# dw08a.net
KiCad netlist of a schematic drawn in EAGLE
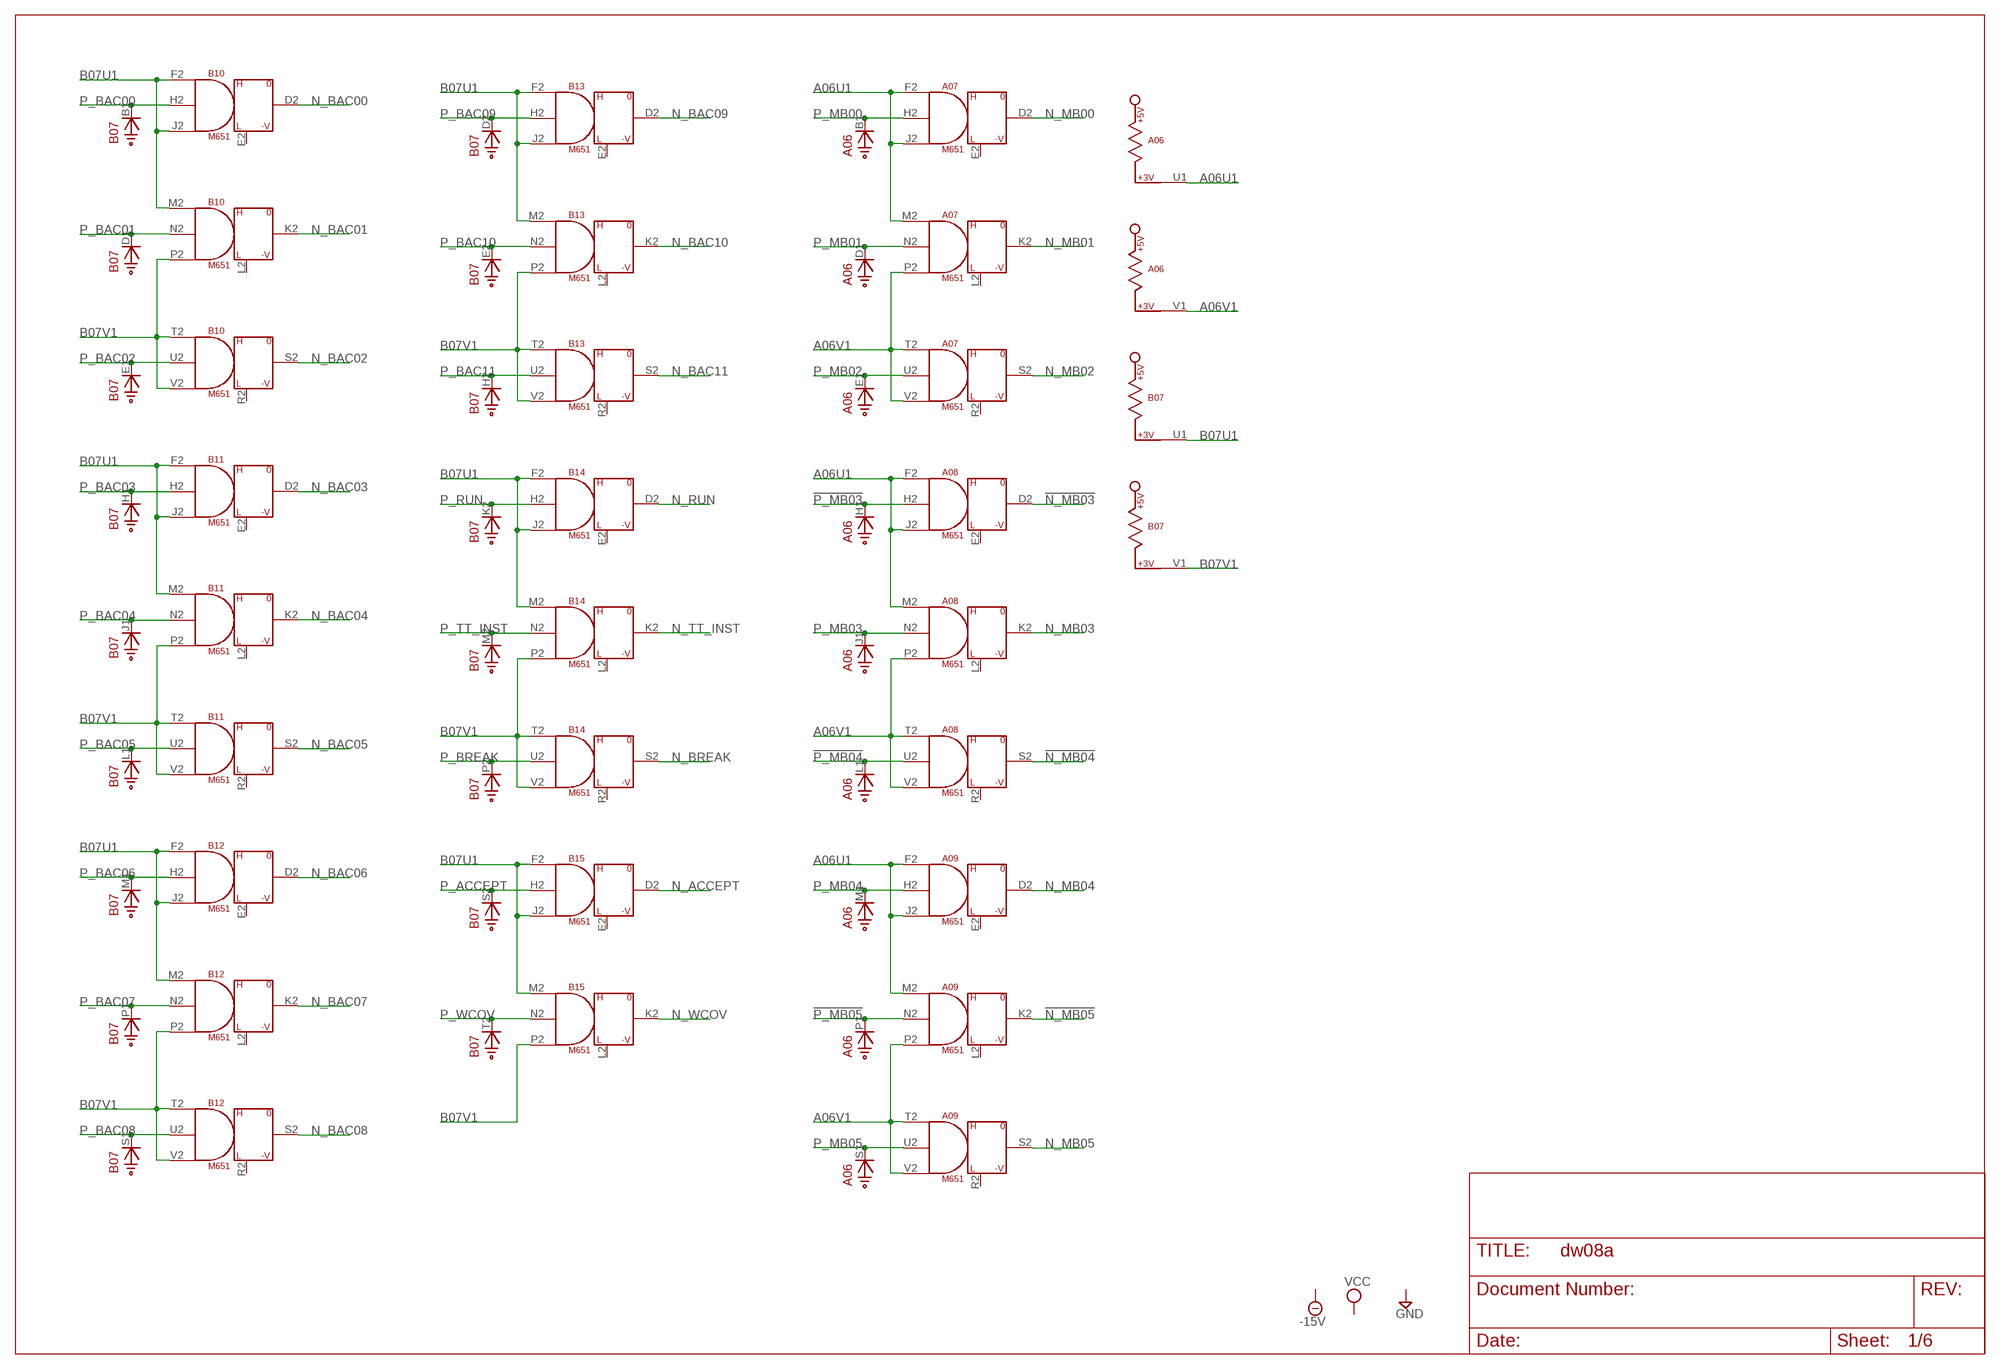
[diagram p0: schematic, sheet 1]
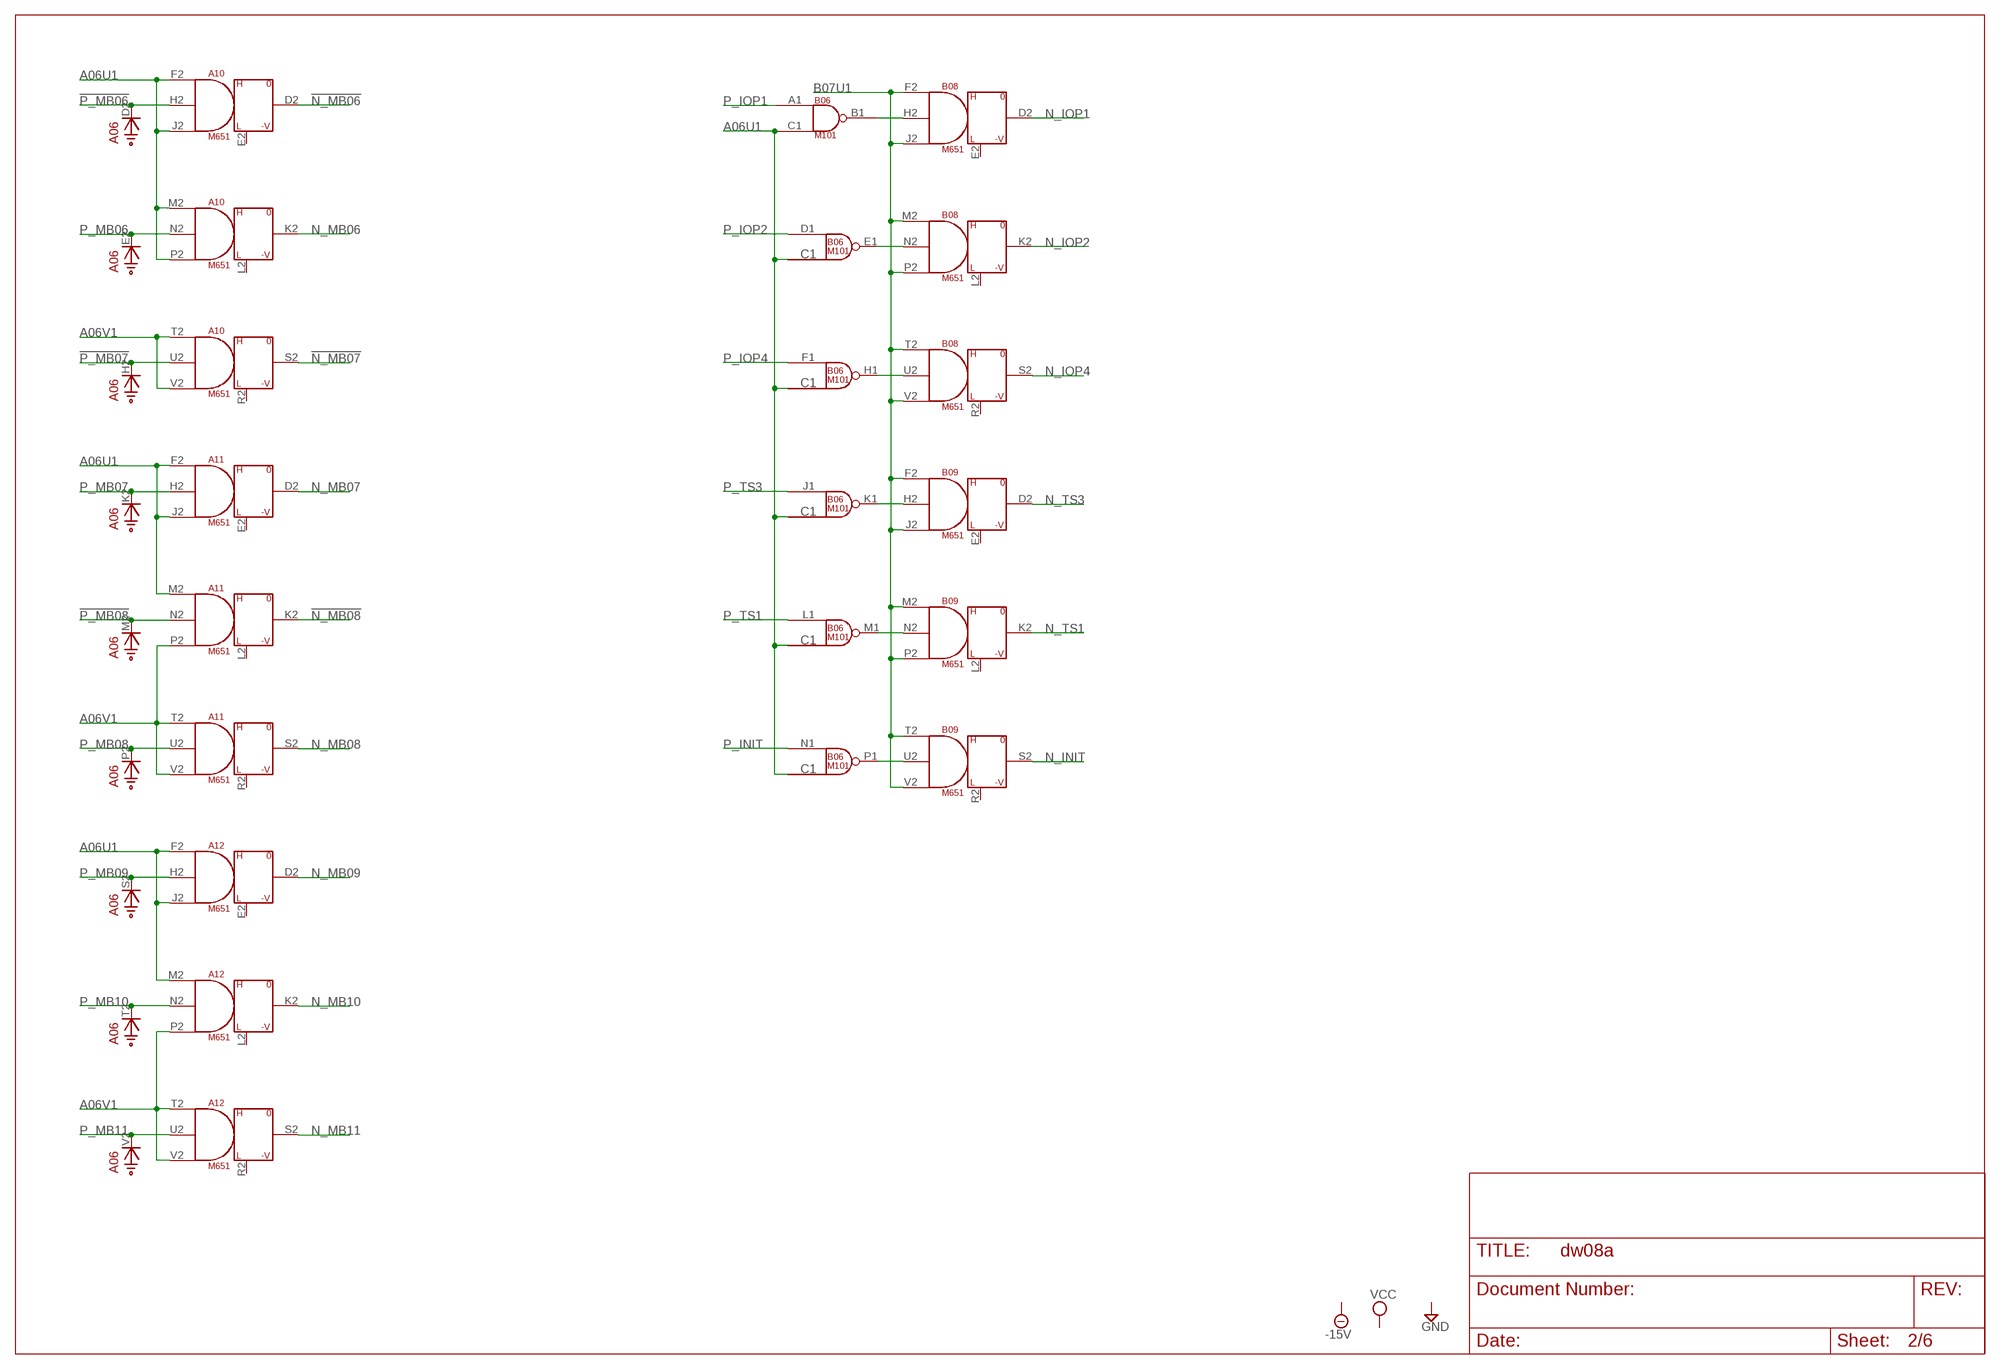
[diagram p1: schematic, sheet 2]
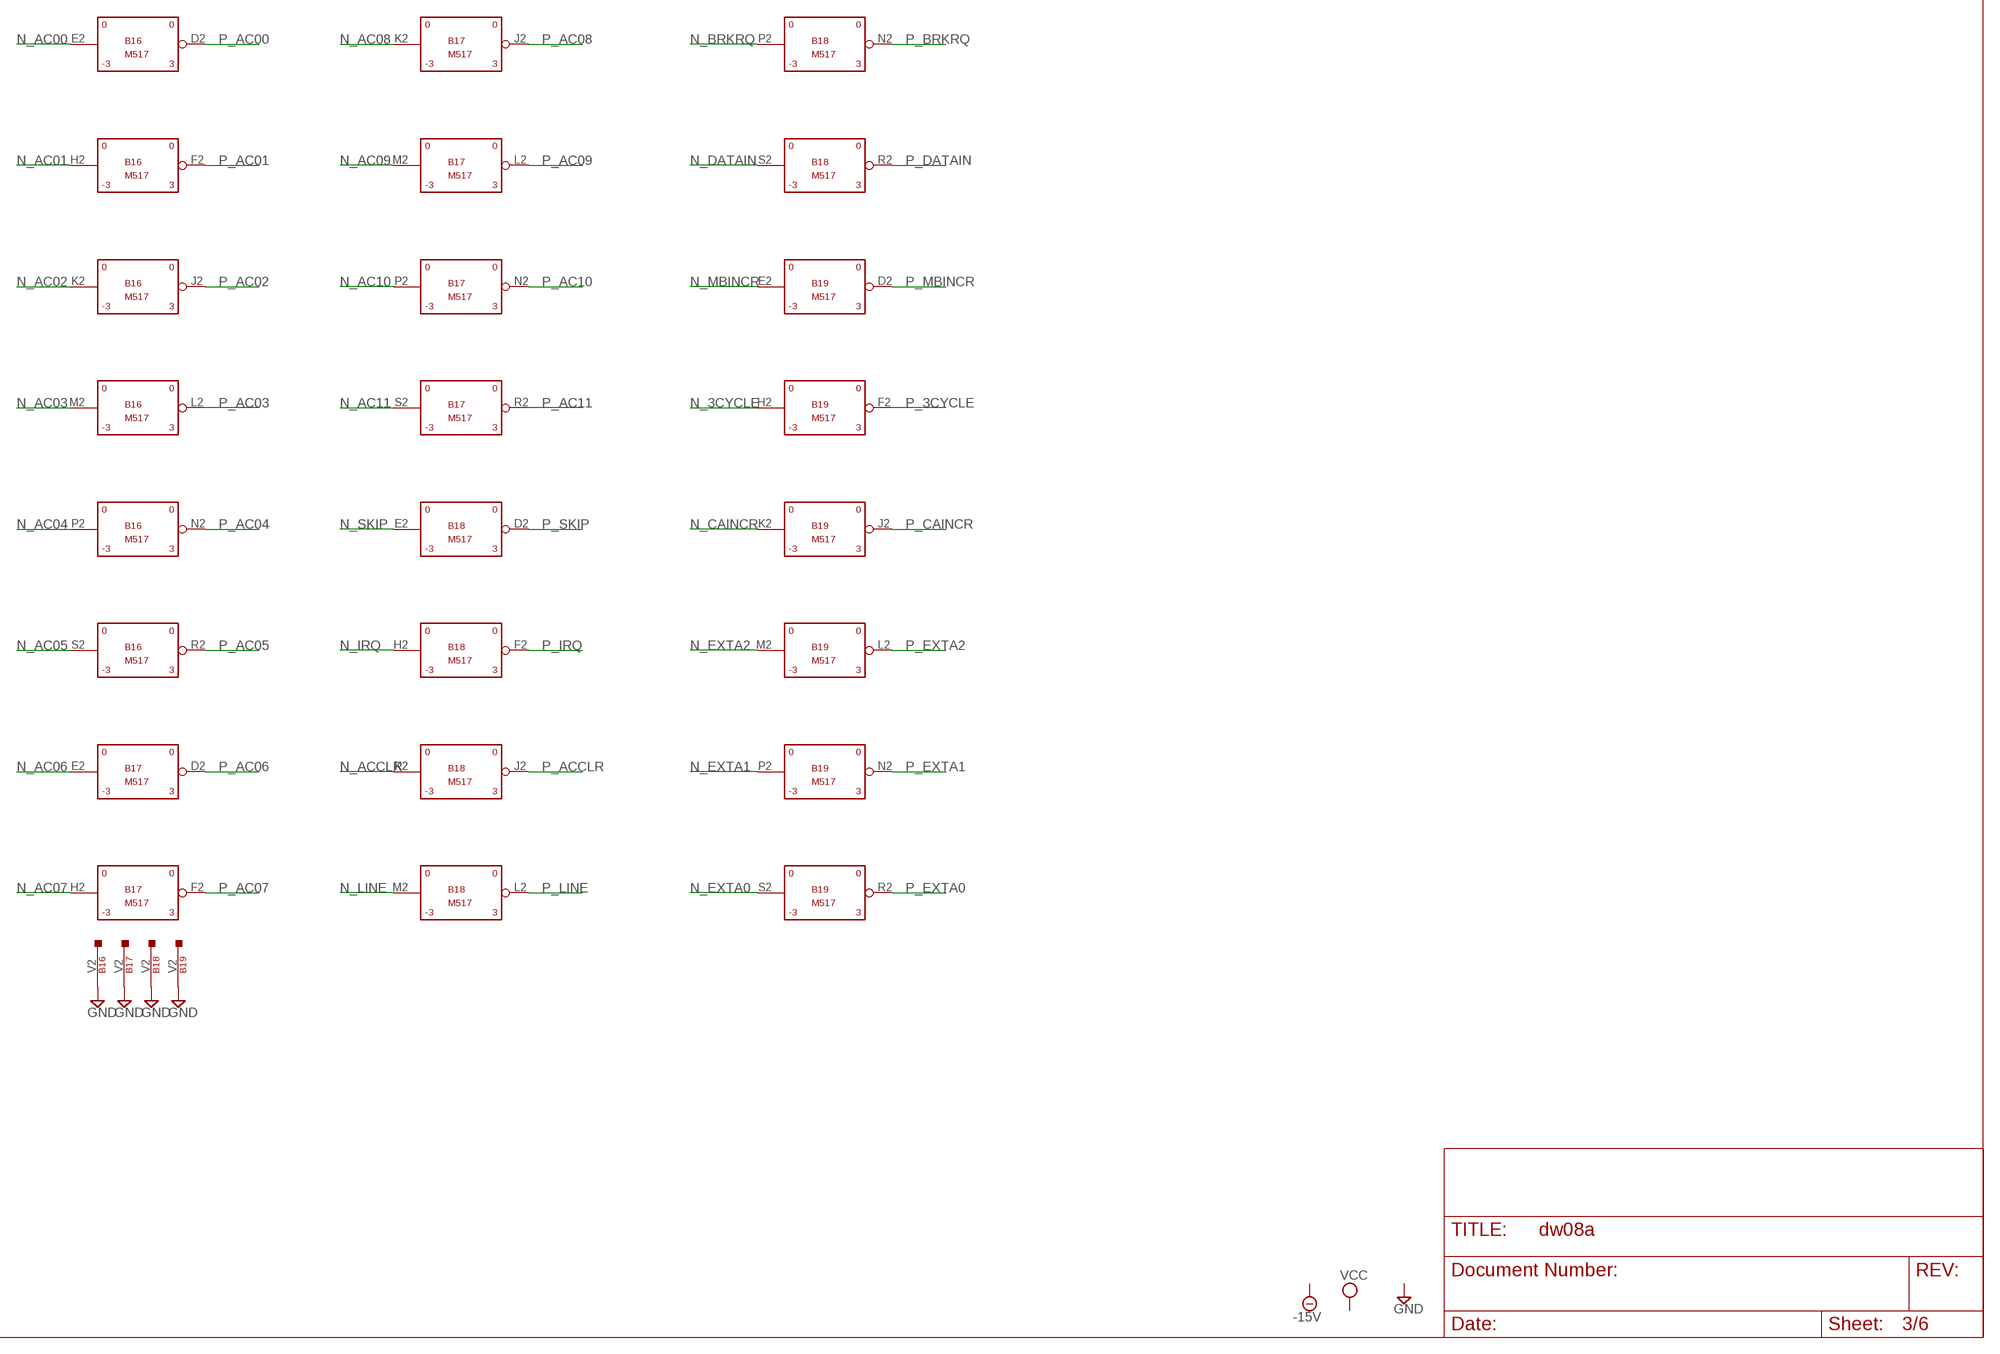
[diagram p2: schematic, sheet 3]
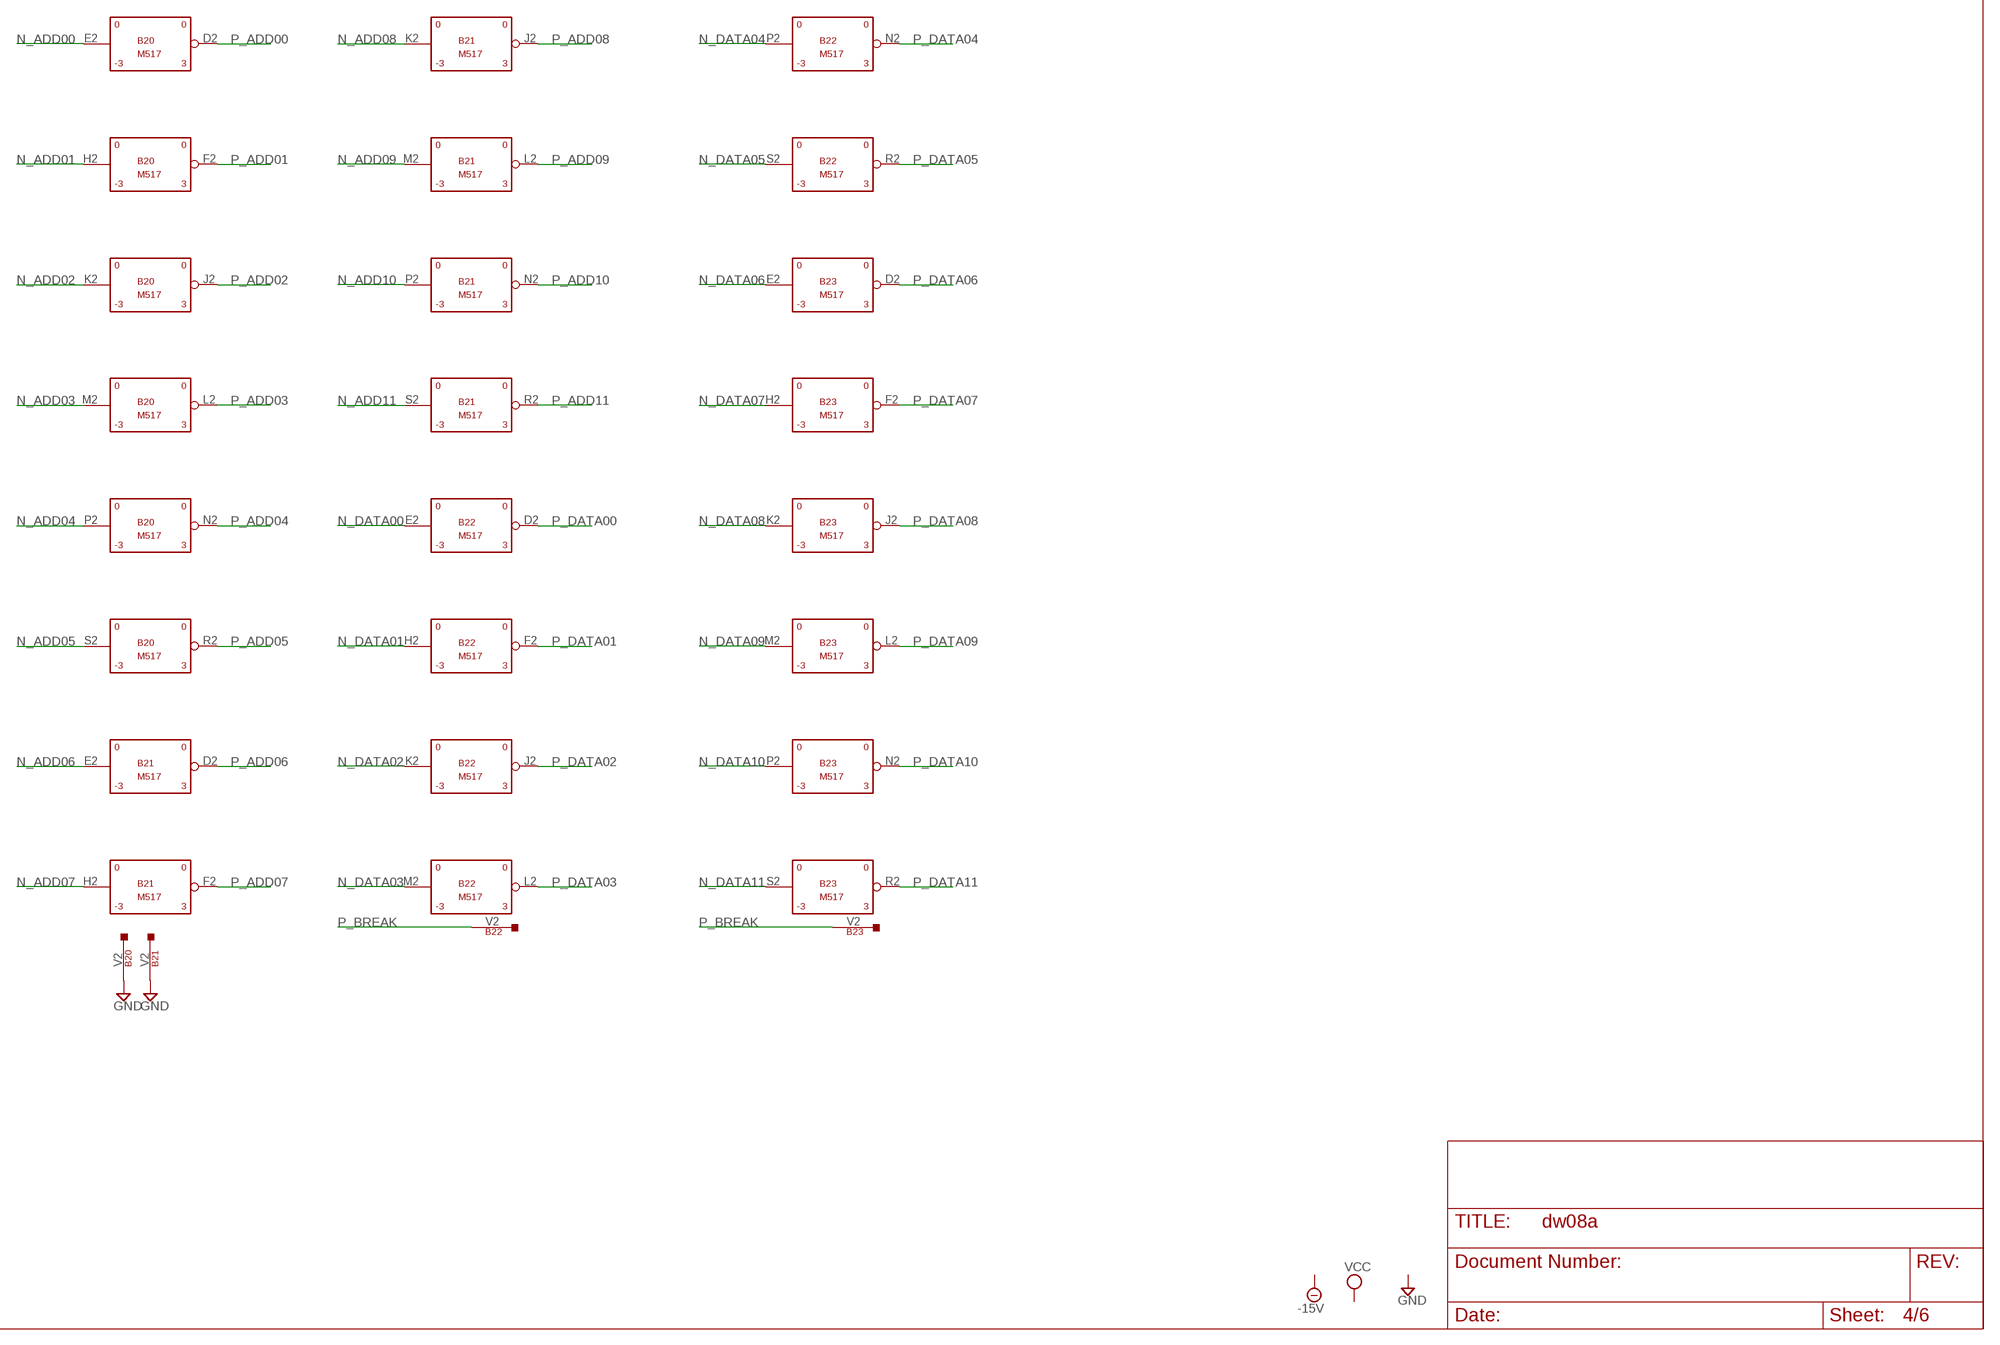
[diagram p3: schematic, sheet 4]
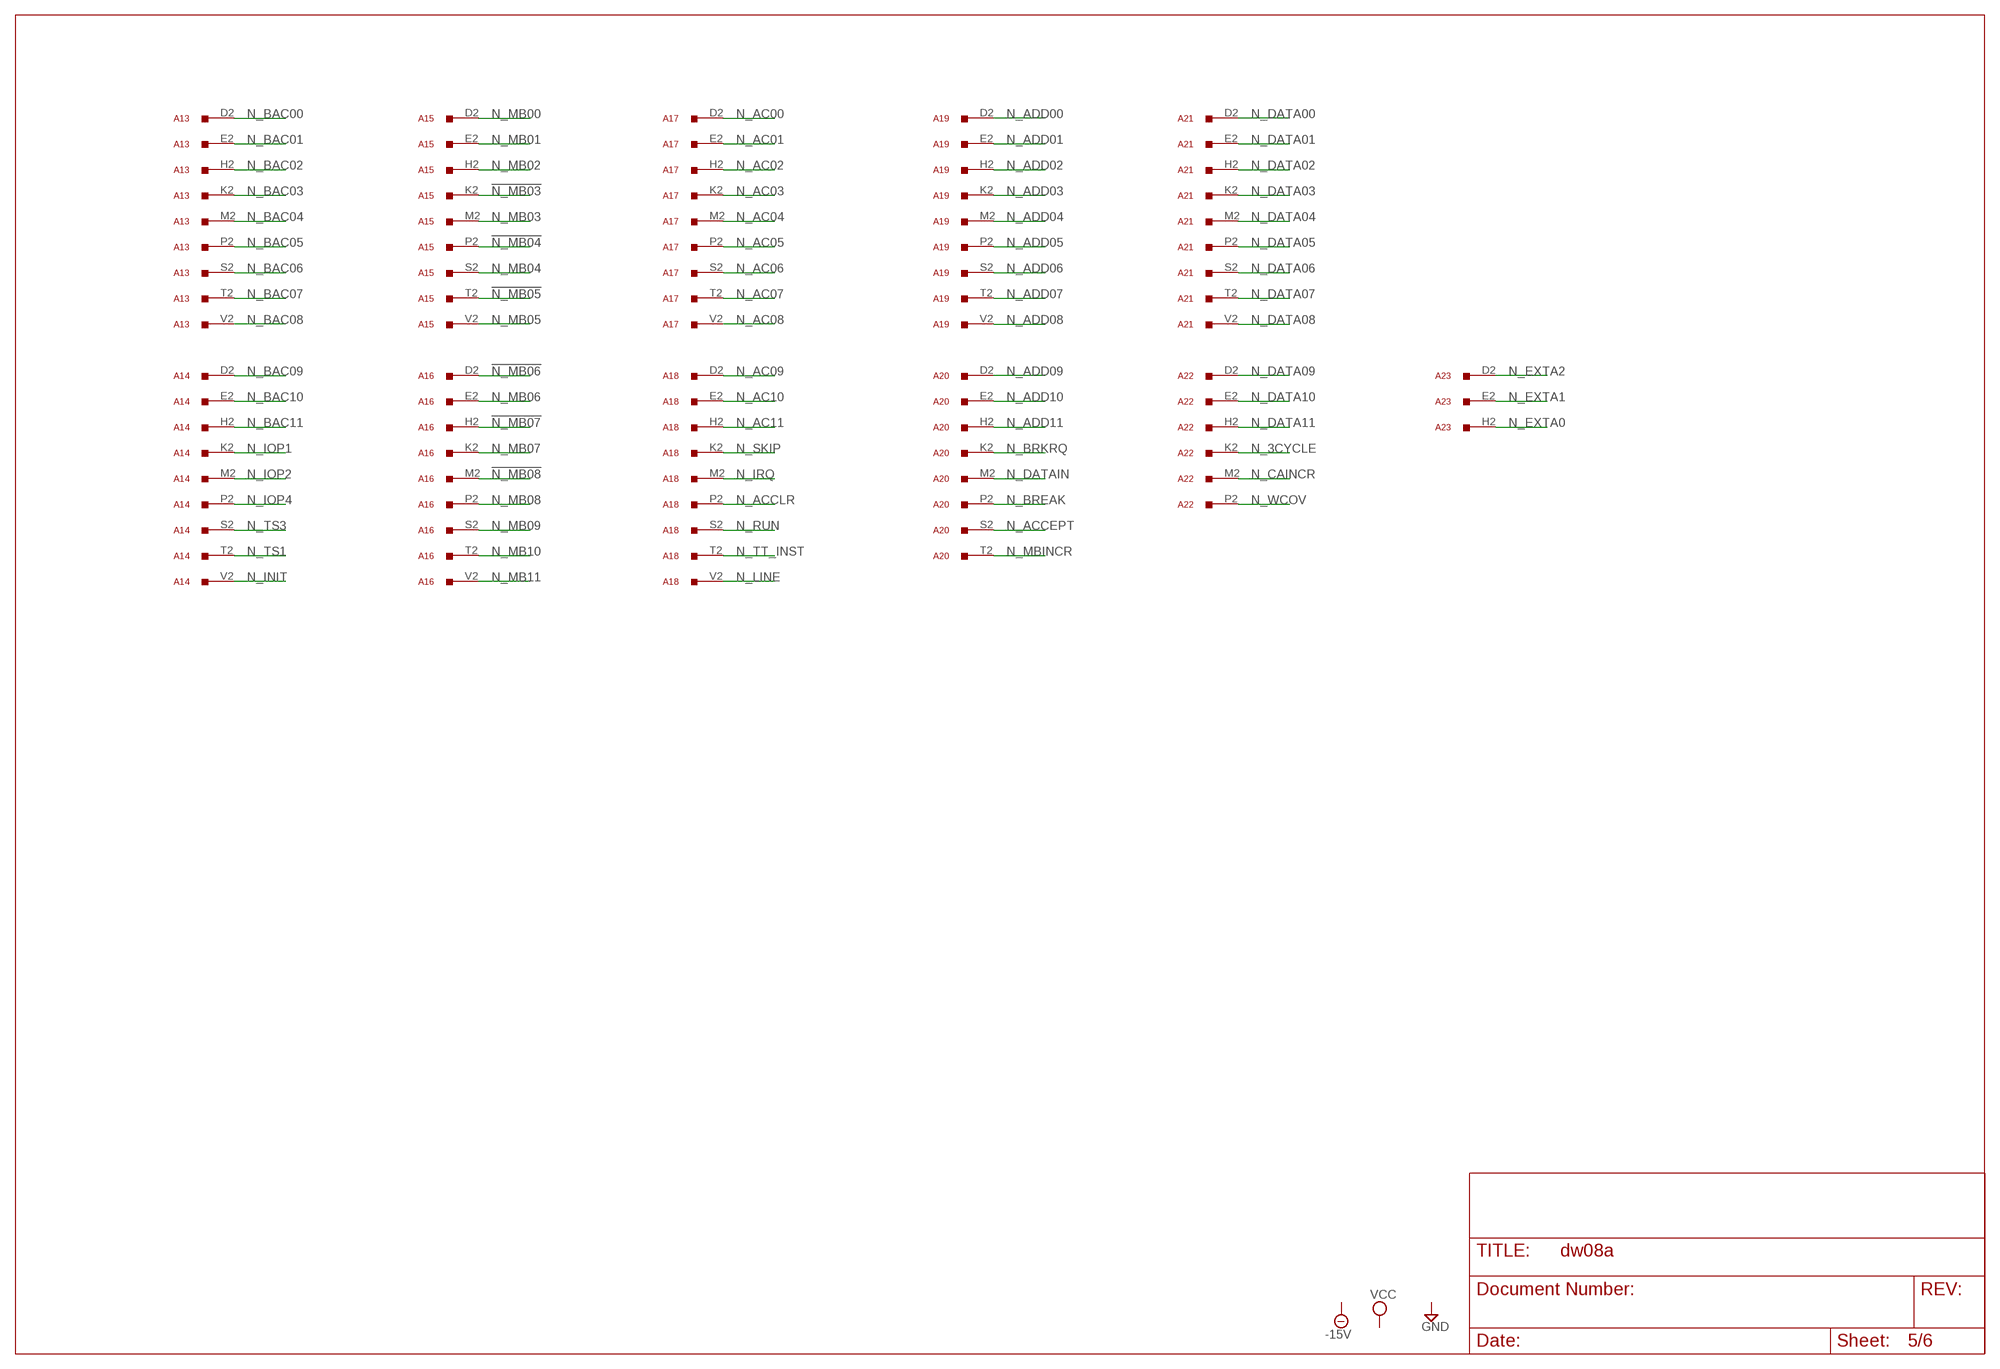
[diagram p4: schematic, sheet 5]
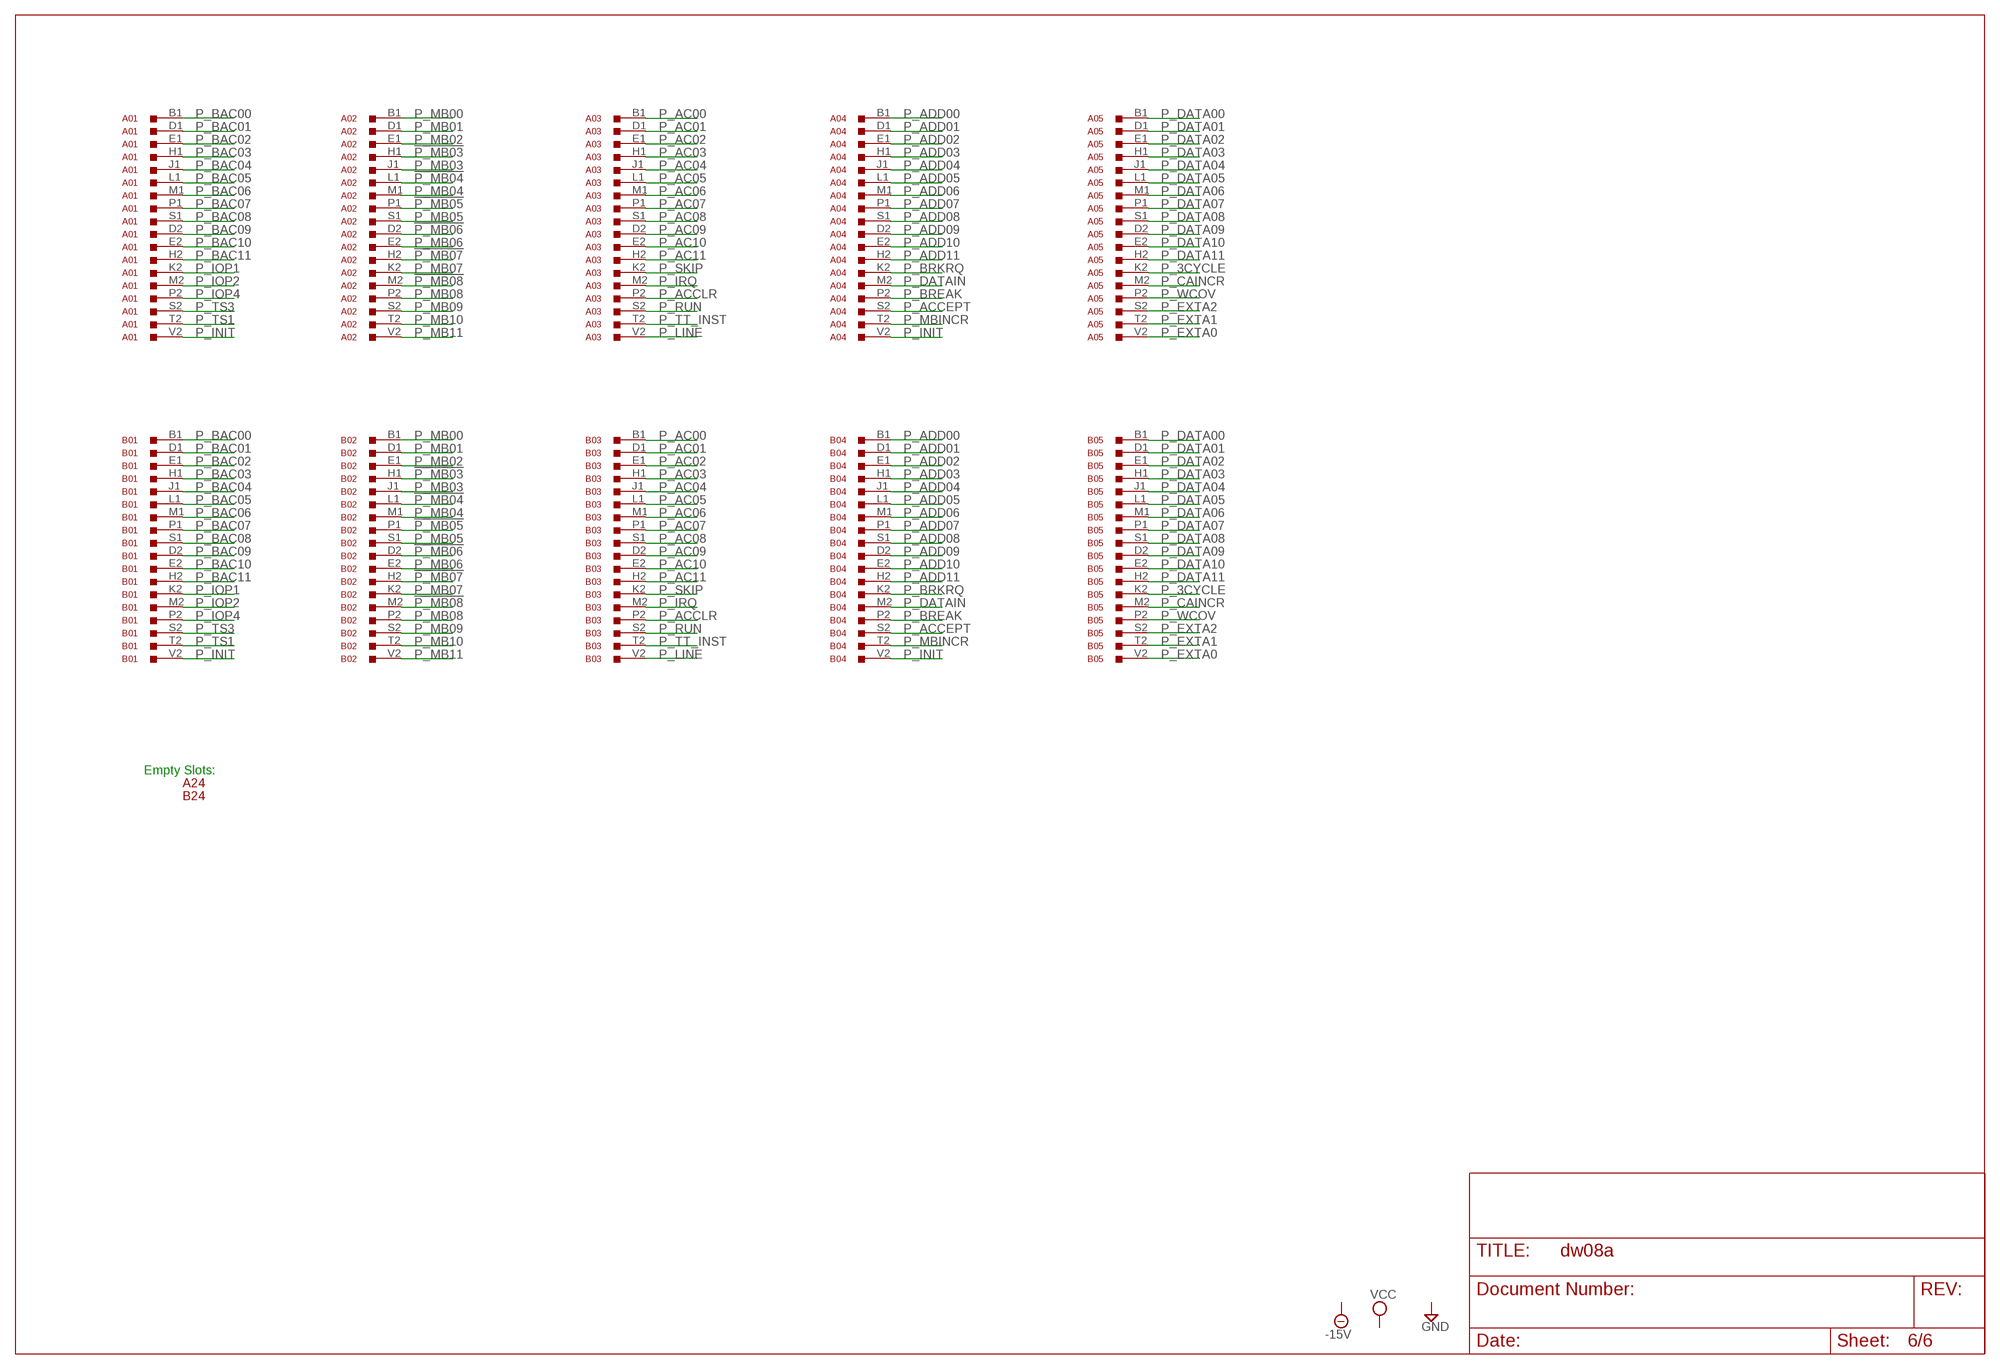
[diagram p5: schematic, sheet 6]

(export (version "E")
  (design (tool "Eeschema 10.0.6"))
  (components
    (comp (ref "A01")
      (value "M903")
      (footprint "eagle-import:H807")
      (libsource (lib "eagle-import") (part "M903"))
    )
    (comp (ref "A02")
      (value "M903")
      (footprint "eagle-import:H807")
      (libsource (lib "eagle-import") (part "M903"))
    )
    (comp (ref "A03")
      (value "M903")
      (footprint "eagle-import:H807")
      (libsource (lib "eagle-import") (part "M903"))
    )
    (comp (ref "A04")
      (value "M903")
      (footprint "eagle-import:H807")
      (libsource (lib "eagle-import") (part "M903"))
    )
    (comp (ref "A05")
      (value "M903")
      (footprint "eagle-import:H807")
      (libsource (lib "eagle-import") (part "M903"))
    )
    (comp (ref "A24")
      (value "H807")
      (footprint "eagle-import:H807")
      (libsource (lib "eagle-import") (part "H807"))
    )
    (comp (ref "B01")
      (value "M903")
      (footprint "eagle-import:H807")
      (libsource (lib "eagle-import") (part "M903"))
    )
    (comp (ref "B02")
      (value "M903")
      (footprint "eagle-import:H807")
      (libsource (lib "eagle-import") (part "M903"))
    )
    (comp (ref "B03")
      (value "M903")
      (footprint "eagle-import:H807")
      (libsource (lib "eagle-import") (part "M903"))
    )
    (comp (ref "B04")
      (value "M903")
      (footprint "eagle-import:H807")
      (libsource (lib "eagle-import") (part "M903"))
    )
    (comp (ref "B05")
      (value "M903")
      (footprint "eagle-import:H807")
      (libsource (lib "eagle-import") (part "M903"))
    )
    (comp (ref "B24")
      (value "H807")
      (footprint "eagle-import:H807")
      (libsource (lib "eagle-import") (part "H807"))
    )
    (comp (ref "A13")
      (value "W011")
      (footprint "eagle-import:H807")
      (libsource (lib "eagle-import") (part "W011"))
    )
    (comp (ref "A14")
      (value "W011")
      (footprint "eagle-import:H807")
      (libsource (lib "eagle-import") (part "W011"))
    )
    (comp (ref "A15")
      (value "W011")
      (footprint "eagle-import:H807")
      (libsource (lib "eagle-import") (part "W011"))
    )
    (comp (ref "A16")
      (value "W011")
      (footprint "eagle-import:H807")
      (libsource (lib "eagle-import") (part "W011"))
    )
    (comp (ref "A17")
      (value "W011")
      (footprint "eagle-import:H807")
      (libsource (lib "eagle-import") (part "W011"))
    )
    (comp (ref "A18")
      (value "W011")
      (footprint "eagle-import:H807")
      (libsource (lib "eagle-import") (part "W011"))
    )
    (comp (ref "A19")
      (value "W011")
      (footprint "eagle-import:H807")
      (libsource (lib "eagle-import") (part "W011"))
    )
    (comp (ref "A20")
      (value "W011")
      (footprint "eagle-import:H807")
      (libsource (lib "eagle-import") (part "W011"))
    )
    (comp (ref "A21")
      (value "W011")
      (footprint "eagle-import:H807")
      (libsource (lib "eagle-import") (part "W011"))
    )
    (comp (ref "A22")
      (value "W011")
      (footprint "eagle-import:H807")
      (libsource (lib "eagle-import") (part "W011"))
    )
    (comp (ref "A23")
      (value "W011")
      (footprint "eagle-import:H807")
      (libsource (lib "eagle-import") (part "W011"))
    )
    (comp (ref "A06")
      (value "M907")
      (footprint "eagle-import:H807")
      (libsource (lib "eagle-import") (part "M907"))
    )
    (comp (ref "A10")
      (value "M651")
      (footprint "eagle-import:H807")
      (libsource (lib "eagle-import") (part "M651"))
    )
    (comp (ref "A11")
      (value "M651")
      (footprint "eagle-import:H807")
      (libsource (lib "eagle-import") (part "M651"))
    )
    (comp (ref "A12")
      (value "M651")
      (footprint "eagle-import:H807")
      (libsource (lib "eagle-import") (part "M651"))
    )
    (comp (ref "B06")
      (value "M101")
      (footprint "eagle-import:H807")
      (libsource (lib "eagle-import") (part "M101"))
    )
    (comp (ref "B08")
      (value "M651")
      (footprint "eagle-import:H807")
      (libsource (lib "eagle-import") (part "M651"))
    )
    (comp (ref "B09")
      (value "M651")
      (footprint "eagle-import:H807")
      (libsource (lib "eagle-import") (part "M651"))
    )
    (comp (ref "B16")
      (value "M517")
      (footprint "eagle-import:H807")
      (libsource (lib "eagle-import") (part "M517"))
    )
    (comp (ref "B17")
      (value "M517")
      (footprint "eagle-import:H807")
      (libsource (lib "eagle-import") (part "M517"))
    )
    (comp (ref "B18")
      (value "M517")
      (footprint "eagle-import:H807")
      (libsource (lib "eagle-import") (part "M517"))
    )
    (comp (ref "B19")
      (value "M517")
      (footprint "eagle-import:H807")
      (libsource (lib "eagle-import") (part "M517"))
    )
    (comp (ref "A07")
      (value "M651")
      (footprint "eagle-import:H807")
      (libsource (lib "eagle-import") (part "M651"))
    )
    (comp (ref "A08")
      (value "M651")
      (footprint "eagle-import:H807")
      (libsource (lib "eagle-import") (part "M651"))
    )
    (comp (ref "A09")
      (value "M651")
      (footprint "eagle-import:H807")
      (libsource (lib "eagle-import") (part "M651"))
    )
    (comp (ref "B07")
      (value "M907")
      (footprint "eagle-import:H807")
      (libsource (lib "eagle-import") (part "M907"))
    )
    (comp (ref "B10")
      (value "M651")
      (footprint "eagle-import:H807")
      (libsource (lib "eagle-import") (part "M651"))
    )
    (comp (ref "B11")
      (value "M651")
      (footprint "eagle-import:H807")
      (libsource (lib "eagle-import") (part "M651"))
    )
    (comp (ref "B12")
      (value "M651")
      (footprint "eagle-import:H807")
      (libsource (lib "eagle-import") (part "M651"))
    )
    (comp (ref "B13")
      (value "M651")
      (footprint "eagle-import:H807")
      (libsource (lib "eagle-import") (part "M651"))
    )
    (comp (ref "B14")
      (value "M651")
      (footprint "eagle-import:H807")
      (libsource (lib "eagle-import") (part "M651"))
    )
    (comp (ref "B15")
      (value "M651")
      (footprint "eagle-import:H807")
      (libsource (lib "eagle-import") (part "M651"))
    )
    (comp (ref "B20")
      (value "M517")
      (footprint "eagle-import:H807")
      (libsource (lib "eagle-import") (part "M517"))
    )
    (comp (ref "B21")
      (value "M517")
      (footprint "eagle-import:H807")
      (libsource (lib "eagle-import") (part "M517"))
    )
    (comp (ref "B22")
      (value "M517")
      (footprint "eagle-import:H807")
      (libsource (lib "eagle-import") (part "M517"))
    )
    (comp (ref "B23")
      (value "M517")
      (footprint "eagle-import:H807")
      (libsource (lib "eagle-import") (part "M517"))
    )
  )
  (nets
    (net (code "2") (name "A06U1") (class "Default")
      (node (ref "A06") (pin "U1") (pinfunction "P$1_U1") (pintype "passive"))
      (node (ref "A07") (pin "F2") (pinfunction "IN1_F2") (pintype "input"))
      (node (ref "A07") (pin "J2") (pinfunction "IN3_J2") (pintype "input"))
      (node (ref "A07") (pin "M2") (pinfunction "IN1_M2") (pintype "input"))
      (node (ref "A08") (pin "F2") (pinfunction "IN1_F2") (pintype "input"))
      (node (ref "A08") (pin "J2") (pinfunction "IN3_J2") (pintype "input"))
      (node (ref "A08") (pin "M2") (pinfunction "IN1_M2") (pintype "input"))
      (node (ref "A09") (pin "F2") (pinfunction "IN1_F2") (pintype "input"))
      (node (ref "A09") (pin "J2") (pinfunction "IN3_J2") (pintype "input"))
      (node (ref "A09") (pin "M2") (pinfunction "IN1_M2") (pintype "input"))
      (node (ref "A10") (pin "F2") (pinfunction "IN1_F2") (pintype "input"))
      (node (ref "A10") (pin "J2") (pinfunction "IN3_J2") (pintype "input"))
      (node (ref "A10") (pin "M2") (pinfunction "IN1_M2") (pintype "input"))
      (node (ref "A10") (pin "P2") (pinfunction "IN3_P2") (pintype "input"))
      (node (ref "A11") (pin "F2") (pinfunction "IN1_F2") (pintype "input"))
      (node (ref "A11") (pin "J2") (pinfunction "IN3_J2") (pintype "input"))
      (node (ref "A11") (pin "M2") (pinfunction "IN1_M2") (pintype "input"))
      (node (ref "A12") (pin "F2") (pinfunction "IN1_F2") (pintype "input"))
      (node (ref "A12") (pin "J2") (pinfunction "IN3_J2") (pintype "input"))
      (node (ref "A12") (pin "M2") (pinfunction "IN1_M2") (pintype "input"))
      (node (ref "B06") (pin "C1") (pinfunction "IN2_C1") (pintype "input"))
    )
    (net (code "3") (name "A06V1") (class "Default")
      (node (ref "A06") (pin "V1") (pinfunction "P$1_V1") (pintype "passive"))
      (node (ref "A07") (pin "P2") (pinfunction "IN3_P2") (pintype "input"))
      (node (ref "A07") (pin "T2") (pinfunction "IN1_T2") (pintype "input"))
      (node (ref "A07") (pin "V2") (pinfunction "IN3_V2") (pintype "input"))
      (node (ref "A08") (pin "P2") (pinfunction "IN3_P2") (pintype "input"))
      (node (ref "A08") (pin "T2") (pinfunction "IN1_T2") (pintype "input"))
      (node (ref "A08") (pin "V2") (pinfunction "IN3_V2") (pintype "input"))
      (node (ref "A09") (pin "P2") (pinfunction "IN3_P2") (pintype "input"))
      (node (ref "A09") (pin "T2") (pinfunction "IN1_T2") (pintype "input"))
      (node (ref "A09") (pin "V2") (pinfunction "IN3_V2") (pintype "input"))
      (node (ref "A10") (pin "T2") (pinfunction "IN1_T2") (pintype "input"))
      (node (ref "A10") (pin "V2") (pinfunction "IN3_V2") (pintype "input"))
      (node (ref "A11") (pin "P2") (pinfunction "IN3_P2") (pintype "input"))
      (node (ref "A11") (pin "T2") (pinfunction "IN1_T2") (pintype "input"))
      (node (ref "A11") (pin "V2") (pinfunction "IN3_V2") (pintype "input"))
      (node (ref "A12") (pin "P2") (pinfunction "IN3_P2") (pintype "input"))
      (node (ref "A12") (pin "T2") (pinfunction "IN1_T2") (pintype "input"))
      (node (ref "A12") (pin "V2") (pinfunction "IN3_V2") (pintype "input"))
    )
    (net (code "4") (name "B07U1") (class "Default")
      (node (ref "B07") (pin "U1") (pinfunction "P$1_U1") (pintype "passive"))
      (node (ref "B08") (pin "F2") (pinfunction "IN1_F2") (pintype "input"))
      (node (ref "B08") (pin "J2") (pinfunction "IN3_J2") (pintype "input"))
      (node (ref "B08") (pin "M2") (pinfunction "IN1_M2") (pintype "input"))
      (node (ref "B08") (pin "P2") (pinfunction "IN3_P2") (pintype "input"))
      (node (ref "B08") (pin "T2") (pinfunction "IN1_T2") (pintype "input"))
      (node (ref "B08") (pin "V2") (pinfunction "IN3_V2") (pintype "input"))
      (node (ref "B09") (pin "F2") (pinfunction "IN1_F2") (pintype "input"))
      (node (ref "B09") (pin "J2") (pinfunction "IN3_J2") (pintype "input"))
      (node (ref "B09") (pin "M2") (pinfunction "IN1_M2") (pintype "input"))
      (node (ref "B09") (pin "P2") (pinfunction "IN3_P2") (pintype "input"))
      (node (ref "B09") (pin "T2") (pinfunction "IN1_T2") (pintype "input"))
      (node (ref "B09") (pin "V2") (pinfunction "IN3_V2") (pintype "input"))
      (node (ref "B10") (pin "F2") (pinfunction "IN1_F2") (pintype "input"))
      (node (ref "B10") (pin "J2") (pinfunction "IN3_J2") (pintype "input"))
      (node (ref "B10") (pin "M2") (pinfunction "IN1_M2") (pintype "input"))
      (node (ref "B11") (pin "F2") (pinfunction "IN1_F2") (pintype "input"))
      (node (ref "B11") (pin "J2") (pinfunction "IN3_J2") (pintype "input"))
      (node (ref "B11") (pin "M2") (pinfunction "IN1_M2") (pintype "input"))
      (node (ref "B12") (pin "F2") (pinfunction "IN1_F2") (pintype "input"))
      (node (ref "B12") (pin "J2") (pinfunction "IN3_J2") (pintype "input"))
      (node (ref "B12") (pin "M2") (pinfunction "IN1_M2") (pintype "input"))
      (node (ref "B13") (pin "F2") (pinfunction "IN1_F2") (pintype "input"))
      (node (ref "B13") (pin "J2") (pinfunction "IN3_J2") (pintype "input"))
      (node (ref "B13") (pin "M2") (pinfunction "IN1_M2") (pintype "input"))
      (node (ref "B14") (pin "F2") (pinfunction "IN1_F2") (pintype "input"))
      (node (ref "B14") (pin "J2") (pinfunction "IN3_J2") (pintype "input"))
      (node (ref "B14") (pin "M2") (pinfunction "IN1_M2") (pintype "input"))
      (node (ref "B15") (pin "F2") (pinfunction "IN1_F2") (pintype "input"))
      (node (ref "B15") (pin "J2") (pinfunction "IN3_J2") (pintype "input"))
      (node (ref "B15") (pin "M2") (pinfunction "IN1_M2") (pintype "input"))
    )
    (net (code "5") (name "B07V1") (class "Default")
      (node (ref "B07") (pin "V1") (pinfunction "P$1_V1") (pintype "passive"))
      (node (ref "B10") (pin "P2") (pinfunction "IN3_P2") (pintype "input"))
      (node (ref "B10") (pin "T2") (pinfunction "IN1_T2") (pintype "input"))
      (node (ref "B10") (pin "V2") (pinfunction "IN3_V2") (pintype "input"))
      (node (ref "B11") (pin "P2") (pinfunction "IN3_P2") (pintype "input"))
      (node (ref "B11") (pin "T2") (pinfunction "IN1_T2") (pintype "input"))
      (node (ref "B11") (pin "V2") (pinfunction "IN3_V2") (pintype "input"))
      (node (ref "B12") (pin "P2") (pinfunction "IN3_P2") (pintype "input"))
      (node (ref "B12") (pin "T2") (pinfunction "IN1_T2") (pintype "input"))
      (node (ref "B12") (pin "V2") (pinfunction "IN3_V2") (pintype "input"))
      (node (ref "B13") (pin "P2") (pinfunction "IN3_P2") (pintype "input"))
      (node (ref "B13") (pin "T2") (pinfunction "IN1_T2") (pintype "input"))
      (node (ref "B13") (pin "V2") (pinfunction "IN3_V2") (pintype "input"))
      (node (ref "B14") (pin "P2") (pinfunction "IN3_P2") (pintype "input"))
      (node (ref "B14") (pin "T2") (pinfunction "IN1_T2") (pintype "input"))
      (node (ref "B14") (pin "V2") (pinfunction "IN3_V2") (pintype "input"))
      (node (ref "B15") (pin "P2") (pinfunction "IN3_P2") (pintype "input"))
    )
    (net (code "6") (name "GND") (class "Default")
      (node (ref "B16") (pin "V2") (pinfunction "P$1_V2") (pintype "input"))
      (node (ref "B17") (pin "V2") (pinfunction "P$1_V2") (pintype "input"))
      (node (ref "B18") (pin "V2") (pinfunction "P$1_V2") (pintype "input"))
      (node (ref "B19") (pin "V2") (pinfunction "P$1_V2") (pintype "input"))
      (node (ref "B20") (pin "V2") (pinfunction "P$1_V2") (pintype "input"))
      (node (ref "B21") (pin "V2") (pinfunction "P$1_V2") (pintype "input"))
    )
    (net (code "7") (name "N_3CYCLE") (class "Default")
      (node (ref "A22") (pin "K2") (pinfunction "P$2_K2") (pintype "bidirectional"))
      (node (ref "B19") (pin "H2") (pinfunction "IN_H2") (pintype "input"))
    )
    (net (code "8") (name "N_AC00") (class "Default")
      (node (ref "A17") (pin "D2") (pinfunction "P$2_D2") (pintype "bidirectional"))
      (node (ref "B16") (pin "E2") (pinfunction "IN_E2") (pintype "input"))
    )
    (net (code "9") (name "N_AC01") (class "Default")
      (node (ref "A17") (pin "E2") (pinfunction "P$2_E2") (pintype "bidirectional"))
      (node (ref "B16") (pin "H2") (pinfunction "IN_H2") (pintype "input"))
    )
    (net (code "10") (name "N_AC02") (class "Default")
      (node (ref "A17") (pin "H2") (pinfunction "P$2_H2") (pintype "bidirectional"))
      (node (ref "B16") (pin "K2") (pinfunction "IN_K2") (pintype "input"))
    )
    (net (code "11") (name "N_AC03") (class "Default")
      (node (ref "A17") (pin "K2") (pinfunction "P$2_K2") (pintype "bidirectional"))
      (node (ref "B16") (pin "M2") (pinfunction "IN_M2") (pintype "input"))
    )
    (net (code "12") (name "N_AC04") (class "Default")
      (node (ref "A17") (pin "M2") (pinfunction "P$2_M2") (pintype "bidirectional"))
      (node (ref "B16") (pin "P2") (pinfunction "IN_P2") (pintype "input"))
    )
    (net (code "13") (name "N_AC05") (class "Default")
      (node (ref "A17") (pin "P2") (pinfunction "P$2_P2") (pintype "bidirectional"))
      (node (ref "B16") (pin "S2") (pinfunction "IN_S2") (pintype "input"))
    )
    (net (code "14") (name "N_AC06") (class "Default")
      (node (ref "A17") (pin "S2") (pinfunction "P$2_S2") (pintype "bidirectional"))
      (node (ref "B17") (pin "E2") (pinfunction "IN_E2") (pintype "input"))
    )
    (net (code "15") (name "N_AC07") (class "Default")
      (node (ref "A17") (pin "T2") (pinfunction "P$2_T2") (pintype "bidirectional"))
      (node (ref "B17") (pin "H2") (pinfunction "IN_H2") (pintype "input"))
    )
    (net (code "16") (name "N_AC08") (class "Default")
      (node (ref "A17") (pin "V2") (pinfunction "P$2_V2") (pintype "bidirectional"))
      (node (ref "B17") (pin "K2") (pinfunction "IN_K2") (pintype "input"))
    )
    (net (code "17") (name "N_AC09") (class "Default")
      (node (ref "A18") (pin "D2") (pinfunction "P$2_D2") (pintype "bidirectional"))
      (node (ref "B17") (pin "M2") (pinfunction "IN_M2") (pintype "input"))
    )
    (net (code "18") (name "N_AC10") (class "Default")
      (node (ref "A18") (pin "E2") (pinfunction "P$2_E2") (pintype "bidirectional"))
      (node (ref "B17") (pin "P2") (pinfunction "IN_P2") (pintype "input"))
    )
    (net (code "19") (name "N_AC11") (class "Default")
      (node (ref "A18") (pin "H2") (pinfunction "P$2_H2") (pintype "bidirectional"))
      (node (ref "B17") (pin "S2") (pinfunction "IN_S2") (pintype "input"))
    )
    (net (code "20") (name "N_ACCEPT") (class "Default")
      (node (ref "A20") (pin "S2") (pinfunction "P$2_S2") (pintype "bidirectional"))
      (node (ref "B15") (pin "D2") (pinfunction "OUT_D2") (pintype "output"))
    )
    (net (code "21") (name "N_ACCLR") (class "Default")
      (node (ref "A18") (pin "P2") (pinfunction "P$2_P2") (pintype "bidirectional"))
      (node (ref "B18") (pin "K2") (pinfunction "IN_K2") (pintype "input"))
    )
    (net (code "22") (name "N_ADD00") (class "Default")
      (node (ref "A19") (pin "D2") (pinfunction "P$2_D2") (pintype "bidirectional"))
      (node (ref "B20") (pin "E2") (pinfunction "IN_E2") (pintype "input"))
    )
    (net (code "23") (name "N_ADD01") (class "Default")
      (node (ref "A19") (pin "E2") (pinfunction "P$2_E2") (pintype "bidirectional"))
      (node (ref "B20") (pin "H2") (pinfunction "IN_H2") (pintype "input"))
    )
    (net (code "24") (name "N_ADD02") (class "Default")
      (node (ref "A19") (pin "H2") (pinfunction "P$2_H2") (pintype "bidirectional"))
      (node (ref "B20") (pin "K2") (pinfunction "IN_K2") (pintype "input"))
    )
    (net (code "25") (name "N_ADD03") (class "Default")
      (node (ref "A19") (pin "K2") (pinfunction "P$2_K2") (pintype "bidirectional"))
      (node (ref "B20") (pin "M2") (pinfunction "IN_M2") (pintype "input"))
    )
    (net (code "26") (name "N_ADD04") (class "Default")
      (node (ref "A19") (pin "M2") (pinfunction "P$2_M2") (pintype "bidirectional"))
      (node (ref "B20") (pin "P2") (pinfunction "IN_P2") (pintype "input"))
    )
    (net (code "27") (name "N_ADD05") (class "Default")
      (node (ref "A19") (pin "P2") (pinfunction "P$2_P2") (pintype "bidirectional"))
      (node (ref "B20") (pin "S2") (pinfunction "IN_S2") (pintype "input"))
    )
    (net (code "28") (name "N_ADD06") (class "Default")
      (node (ref "A19") (pin "S2") (pinfunction "P$2_S2") (pintype "bidirectional"))
      (node (ref "B21") (pin "E2") (pinfunction "IN_E2") (pintype "input"))
    )
    (net (code "29") (name "N_ADD07") (class "Default")
      (node (ref "A19") (pin "T2") (pinfunction "P$2_T2") (pintype "bidirectional"))
      (node (ref "B21") (pin "H2") (pinfunction "IN_H2") (pintype "input"))
    )
    (net (code "30") (name "N_ADD08") (class "Default")
      (node (ref "A19") (pin "V2") (pinfunction "P$2_V2") (pintype "bidirectional"))
      (node (ref "B21") (pin "K2") (pinfunction "IN_K2") (pintype "input"))
    )
    (net (code "31") (name "N_ADD09") (class "Default")
      (node (ref "A20") (pin "D2") (pinfunction "P$2_D2") (pintype "bidirectional"))
      (node (ref "B21") (pin "M2") (pinfunction "IN_M2") (pintype "input"))
    )
    (net (code "32") (name "N_ADD10") (class "Default")
      (node (ref "A20") (pin "E2") (pinfunction "P$2_E2") (pintype "bidirectional"))
      (node (ref "B21") (pin "P2") (pinfunction "IN_P2") (pintype "input"))
    )
    (net (code "33") (name "N_ADD11") (class "Default")
      (node (ref "A20") (pin "H2") (pinfunction "P$2_H2") (pintype "bidirectional"))
      (node (ref "B21") (pin "S2") (pinfunction "IN_S2") (pintype "input"))
    )
    (net (code "34") (name "N_BAC00") (class "Default")
      (node (ref "A13") (pin "D2") (pinfunction "P$2_D2") (pintype "bidirectional"))
      (node (ref "B10") (pin "D2") (pinfunction "OUT_D2") (pintype "output"))
    )
    (net (code "35") (name "N_BAC01") (class "Default")
      (node (ref "A13") (pin "E2") (pinfunction "P$2_E2") (pintype "bidirectional"))
      (node (ref "B10") (pin "K2") (pinfunction "OUT_K2") (pintype "output"))
    )
    (net (code "36") (name "N_BAC02") (class "Default")
      (node (ref "A13") (pin "H2") (pinfunction "P$2_H2") (pintype "bidirectional"))
      (node (ref "B10") (pin "S2") (pinfunction "OUT_S2") (pintype "output"))
    )
    (net (code "37") (name "N_BAC03") (class "Default")
      (node (ref "A13") (pin "K2") (pinfunction "P$2_K2") (pintype "bidirectional"))
      (node (ref "B11") (pin "D2") (pinfunction "OUT_D2") (pintype "output"))
    )
    (net (code "38") (name "N_BAC04") (class "Default")
      (node (ref "A13") (pin "M2") (pinfunction "P$2_M2") (pintype "bidirectional"))
      (node (ref "B11") (pin "K2") (pinfunction "OUT_K2") (pintype "output"))
    )
    (net (code "39") (name "N_BAC05") (class "Default")
      (node (ref "A13") (pin "P2") (pinfunction "P$2_P2") (pintype "bidirectional"))
      (node (ref "B11") (pin "S2") (pinfunction "OUT_S2") (pintype "output"))
    )
    (net (code "40") (name "N_BAC06") (class "Default")
      (node (ref "A13") (pin "S2") (pinfunction "P$2_S2") (pintype "bidirectional"))
      (node (ref "B12") (pin "D2") (pinfunction "OUT_D2") (pintype "output"))
    )
    (net (code "41") (name "N_BAC07") (class "Default")
      (node (ref "A13") (pin "T2") (pinfunction "P$2_T2") (pintype "bidirectional"))
      (node (ref "B12") (pin "K2") (pinfunction "OUT_K2") (pintype "output"))
    )
    (net (code "42") (name "N_BAC08") (class "Default")
      (node (ref "A13") (pin "V2") (pinfunction "P$2_V2") (pintype "bidirectional"))
      (node (ref "B12") (pin "S2") (pinfunction "OUT_S2") (pintype "output"))
    )
    (net (code "43") (name "N_BAC09") (class "Default")
      (node (ref "A14") (pin "D2") (pinfunction "P$2_D2") (pintype "bidirectional"))
      (node (ref "B13") (pin "D2") (pinfunction "OUT_D2") (pintype "output"))
    )
    (net (code "44") (name "N_BAC10") (class "Default")
      (node (ref "A14") (pin "E2") (pinfunction "P$2_E2") (pintype "bidirectional"))
      (node (ref "B13") (pin "K2") (pinfunction "OUT_K2") (pintype "output"))
    )
    (net (code "45") (name "N_BAC11") (class "Default")
      (node (ref "A14") (pin "H2") (pinfunction "P$2_H2") (pintype "bidirectional"))
      (node (ref "B13") (pin "S2") (pinfunction "OUT_S2") (pintype "output"))
    )
    (net (code "46") (name "N_BREAK") (class "Default")
      (node (ref "A20") (pin "P2") (pinfunction "P$2_P2") (pintype "bidirectional"))
      (node (ref "B14") (pin "S2") (pinfunction "OUT_S2") (pintype "output"))
    )
    (net (code "47") (name "N_BRKRQ") (class "Default")
      (node (ref "A20") (pin "K2") (pinfunction "P$2_K2") (pintype "bidirectional"))
      (node (ref "B18") (pin "P2") (pinfunction "IN_P2") (pintype "input"))
    )
    (net (code "48") (name "N_CAINCR") (class "Default")
      (node (ref "A22") (pin "M2") (pinfunction "P$2_M2") (pintype "bidirectional"))
      (node (ref "B19") (pin "K2") (pinfunction "IN_K2") (pintype "input"))
    )
    (net (code "49") (name "N_DATA00") (class "Default")
      (node (ref "A21") (pin "D2") (pinfunction "P$2_D2") (pintype "bidirectional"))
      (node (ref "B22") (pin "E2") (pinfunction "IN_E2") (pintype "input"))
    )
    (net (code "50") (name "N_DATA01") (class "Default")
      (node (ref "A21") (pin "E2") (pinfunction "P$2_E2") (pintype "bidirectional"))
      (node (ref "B22") (pin "H2") (pinfunction "IN_H2") (pintype "input"))
    )
    (net (code "51") (name "N_DATA02") (class "Default")
      (node (ref "A21") (pin "H2") (pinfunction "P$2_H2") (pintype "bidirectional"))
      (node (ref "B22") (pin "K2") (pinfunction "IN_K2") (pintype "input"))
    )
    (net (code "52") (name "N_DATA03") (class "Default")
      (node (ref "A21") (pin "K2") (pinfunction "P$2_K2") (pintype "bidirectional"))
      (node (ref "B22") (pin "M2") (pinfunction "IN_M2") (pintype "input"))
    )
    (net (code "53") (name "N_DATA04") (class "Default")
      (node (ref "A21") (pin "M2") (pinfunction "P$2_M2") (pintype "bidirectional"))
      (node (ref "B22") (pin "P2") (pinfunction "IN_P2") (pintype "input"))
    )
    (net (code "54") (name "N_DATA05") (class "Default")
      (node (ref "A21") (pin "P2") (pinfunction "P$2_P2") (pintype "bidirectional"))
      (node (ref "B22") (pin "S2") (pinfunction "IN_S2") (pintype "input"))
    )
    (net (code "55") (name "N_DATA06") (class "Default")
      (node (ref "A21") (pin "S2") (pinfunction "P$2_S2") (pintype "bidirectional"))
      (node (ref "B23") (pin "E2") (pinfunction "IN_E2") (pintype "input"))
    )
    (net (code "56") (name "N_DATA07") (class "Default")
      (node (ref "A21") (pin "T2") (pinfunction "P$2_T2") (pintype "bidirectional"))
      (node (ref "B23") (pin "H2") (pinfunction "IN_H2") (pintype "input"))
    )
    (net (code "57") (name "N_DATA08") (class "Default")
      (node (ref "A21") (pin "V2") (pinfunction "P$2_V2") (pintype "bidirectional"))
      (node (ref "B23") (pin "K2") (pinfunction "IN_K2") (pintype "input"))
    )
    (net (code "58") (name "N_DATA09") (class "Default")
      (node (ref "A22") (pin "D2") (pinfunction "P$2_D2") (pintype "bidirectional"))
      (node (ref "B23") (pin "M2") (pinfunction "IN_M2") (pintype "input"))
    )
    (net (code "59") (name "N_DATA10") (class "Default")
      (node (ref "A22") (pin "E2") (pinfunction "P$2_E2") (pintype "bidirectional"))
      (node (ref "B23") (pin "P2") (pinfunction "IN_P2") (pintype "input"))
    )
    (net (code "60") (name "N_DATA11") (class "Default")
      (node (ref "A22") (pin "H2") (pinfunction "P$2_H2") (pintype "bidirectional"))
      (node (ref "B23") (pin "S2") (pinfunction "IN_S2") (pintype "input"))
    )
    (net (code "61") (name "N_DATAIN") (class "Default")
      (node (ref "A20") (pin "M2") (pinfunction "P$2_M2") (pintype "bidirectional"))
      (node (ref "B18") (pin "S2") (pinfunction "IN_S2") (pintype "input"))
    )
    (net (code "62") (name "N_EXTA0") (class "Default")
      (node (ref "A23") (pin "H2") (pinfunction "P$2_H2") (pintype "bidirectional"))
      (node (ref "B19") (pin "S2") (pinfunction "IN_S2") (pintype "input"))
    )
    (net (code "63") (name "N_EXTA1") (class "Default")
      (node (ref "A23") (pin "E2") (pinfunction "P$2_E2") (pintype "bidirectional"))
      (node (ref "B19") (pin "P2") (pinfunction "IN_P2") (pintype "input"))
    )
    (net (code "64") (name "N_EXTA2") (class "Default")
      (node (ref "A23") (pin "D2") (pinfunction "P$2_D2") (pintype "bidirectional"))
      (node (ref "B19") (pin "M2") (pinfunction "IN_M2") (pintype "input"))
    )
    (net (code "65") (name "N_INIT") (class "Default")
      (node (ref "A14") (pin "V2") (pinfunction "P$2_V2") (pintype "bidirectional"))
      (node (ref "B09") (pin "S2") (pinfunction "OUT_S2") (pintype "output"))
    )
    (net (code "66") (name "N_IOP1") (class "Default")
      (node (ref "A14") (pin "K2") (pinfunction "P$2_K2") (pintype "bidirectional"))
      (node (ref "B08") (pin "D2") (pinfunction "OUT_D2") (pintype "output"))
    )
    (net (code "67") (name "N_IOP2") (class "Default")
      (node (ref "A14") (pin "M2") (pinfunction "P$2_M2") (pintype "bidirectional"))
      (node (ref "B08") (pin "K2") (pinfunction "OUT_K2") (pintype "output"))
    )
    (net (code "68") (name "N_IOP4") (class "Default")
      (node (ref "A14") (pin "P2") (pinfunction "P$2_P2") (pintype "bidirectional"))
      (node (ref "B08") (pin "S2") (pinfunction "OUT_S2") (pintype "output"))
    )
    (net (code "69") (name "N_IRQ") (class "Default")
      (node (ref "A18") (pin "M2") (pinfunction "P$2_M2") (pintype "bidirectional"))
      (node (ref "B18") (pin "H2") (pinfunction "IN_H2") (pintype "input"))
    )
    (net (code "70") (name "N_LINE") (class "Default")
      (node (ref "A18") (pin "V2") (pinfunction "P$2_V2") (pintype "bidirectional"))
      (node (ref "B18") (pin "M2") (pinfunction "IN_M2") (pintype "input"))
    )
    (net (code "71") (name "N_MB00") (class "Default")
      (node (ref "A07") (pin "D2") (pinfunction "OUT_D2") (pintype "output"))
      (node (ref "A15") (pin "D2") (pinfunction "P$2_D2") (pintype "bidirectional"))
    )
    (net (code "72") (name "N_MB01") (class "Default")
      (node (ref "A07") (pin "K2") (pinfunction "OUT_K2") (pintype "output"))
      (node (ref "A15") (pin "E2") (pinfunction "P$2_E2") (pintype "bidirectional"))
    )
    (net (code "73") (name "N_MB02") (class "Default")
      (node (ref "A07") (pin "S2") (pinfunction "OUT_S2") (pintype "output"))
      (node (ref "A15") (pin "H2") (pinfunction "P$2_H2") (pintype "bidirectional"))
    )
    (net (code "74") (name "N_MB03") (class "Default")
      (node (ref "A08") (pin "K2") (pinfunction "OUT_K2") (pintype "output"))
      (node (ref "A15") (pin "M2") (pinfunction "P$2_M2") (pintype "bidirectional"))
    )
    (net (code "75") (name "N_MB04") (class "Default")
      (node (ref "A09") (pin "D2") (pinfunction "OUT_D2") (pintype "output"))
      (node (ref "A15") (pin "S2") (pinfunction "P$2_S2") (pintype "bidirectional"))
    )
    (net (code "76") (name "N_MB05") (class "Default")
      (node (ref "A09") (pin "S2") (pinfunction "OUT_S2") (pintype "output"))
      (node (ref "A15") (pin "V2") (pinfunction "P$2_V2") (pintype "bidirectional"))
    )
    (net (code "77") (name "N_MB06") (class "Default")
      (node (ref "A10") (pin "K2") (pinfunction "OUT_K2") (pintype "output"))
      (node (ref "A16") (pin "E2") (pinfunction "P$2_E2") (pintype "bidirectional"))
    )
    (net (code "78") (name "N_MB07") (class "Default")
      (node (ref "A11") (pin "D2") (pinfunction "OUT_D2") (pintype "output"))
      (node (ref "A16") (pin "K2") (pinfunction "P$2_K2") (pintype "bidirectional"))
    )
    (net (code "79") (name "N_MB08") (class "Default")
      (node (ref "A11") (pin "S2") (pinfunction "OUT_S2") (pintype "output"))
      (node (ref "A16") (pin "P2") (pinfunction "P$2_P2") (pintype "bidirectional"))
    )
    (net (code "80") (name "N_MB09") (class "Default")
      (node (ref "A12") (pin "D2") (pinfunction "OUT_D2") (pintype "output"))
      (node (ref "A16") (pin "S2") (pinfunction "P$2_S2") (pintype "bidirectional"))
    )
    (net (code "81") (name "N_MB10") (class "Default")
      (node (ref "A12") (pin "K2") (pinfunction "OUT_K2") (pintype "output"))
      (node (ref "A16") (pin "T2") (pinfunction "P$2_T2") (pintype "bidirectional"))
    )
    (net (code "82") (name "N_MB11") (class "Default")
      (node (ref "A12") (pin "S2") (pinfunction "OUT_S2") (pintype "output"))
      (node (ref "A16") (pin "V2") (pinfunction "P$2_V2") (pintype "bidirectional"))
    )
    (net (code "83") (name "N_MBINCR") (class "Default")
      (node (ref "A20") (pin "T2") (pinfunction "P$2_T2") (pintype "bidirectional"))
      (node (ref "B19") (pin "E2") (pinfunction "IN_E2") (pintype "input"))
    )
    (net (code "84") (name "N_RUN") (class "Default")
      (node (ref "A18") (pin "S2") (pinfunction "P$2_S2") (pintype "bidirectional"))
      (node (ref "B14") (pin "D2") (pinfunction "OUT_D2") (pintype "output"))
    )
    (net (code "85") (name "N_SKIP") (class "Default")
      (node (ref "A18") (pin "K2") (pinfunction "P$2_K2") (pintype "bidirectional"))
      (node (ref "B18") (pin "E2") (pinfunction "IN_E2") (pintype "input"))
    )
    (net (code "86") (name "N_TS1") (class "Default")
      (node (ref "A14") (pin "T2") (pinfunction "P$2_T2") (pintype "bidirectional"))
      (node (ref "B09") (pin "K2") (pinfunction "OUT_K2") (pintype "output"))
    )
    (net (code "87") (name "N_TS3") (class "Default")
      (node (ref "A14") (pin "S2") (pinfunction "P$2_S2") (pintype "bidirectional"))
      (node (ref "B09") (pin "D2") (pinfunction "OUT_D2") (pintype "output"))
    )
    (net (code "88") (name "N_TT_INST") (class "Default")
      (node (ref "A18") (pin "T2") (pinfunction "P$2_T2") (pintype "bidirectional"))
      (node (ref "B14") (pin "K2") (pinfunction "OUT_K2") (pintype "output"))
    )
    (net (code "89") (name "N_WCOV") (class "Default")
      (node (ref "A22") (pin "P2") (pinfunction "P$2_P2") (pintype "bidirectional"))
      (node (ref "B15") (pin "K2") (pinfunction "OUT_K2") (pintype "output"))
    )
    (net (code "90") (name "Net-(B06A-OUT)") (class "Default")
      (node (ref "B06") (pin "B1") (pinfunction "OUT_B1") (pintype "output"))
      (node (ref "B08") (pin "H2") (pinfunction "IN2_H2") (pintype "input"))
    )
    (net (code "91") (name "Net-(B06B-OUT)") (class "Default")
      (node (ref "B06") (pin "E1") (pinfunction "OUT_E1") (pintype "output"))
      (node (ref "B08") (pin "N2") (pinfunction "IN2_N2") (pintype "input"))
    )
    (net (code "92") (name "Net-(B06F-OUT)") (class "Default")
      (node (ref "B06") (pin "H1") (pinfunction "OUT_H1") (pintype "output"))
      (node (ref "B08") (pin "U2") (pinfunction "IN2_U2") (pintype "input"))
    )
    (net (code "93") (name "Net-(B06H-OUT)") (class "Default")
      (node (ref "B06") (pin "K1") (pinfunction "OUT_K1") (pintype "output"))
      (node (ref "B09") (pin "H2") (pinfunction "IN2_H2") (pintype "input"))
    )
    (net (code "94") (name "Net-(B06J-OUT)") (class "Default")
      (node (ref "B06") (pin "M1") (pinfunction "OUT_M1") (pintype "output"))
      (node (ref "B09") (pin "N2") (pinfunction "IN2_N2") (pintype "input"))
    )
    (net (code "95") (name "Net-(B06L-OUT)") (class "Default")
      (node (ref "B06") (pin "P1") (pinfunction "OUT_P1") (pintype "output"))
      (node (ref "B09") (pin "U2") (pinfunction "IN2_U2") (pintype "input"))
    )
    (net (code "96") (name "P_3CYCLE") (class "Default")
      (node (ref "A05") (pin "K2") (pinfunction "P$2_K2") (pintype "bidirectional"))
      (node (ref "B05") (pin "K2") (pinfunction "P$2_K2") (pintype "bidirectional"))
      (node (ref "B19") (pin "F2") (pinfunction "OUT_F2") (pintype "output"))
    )
    (net (code "97") (name "P_AC00") (class "Default")
      (node (ref "A03") (pin "B1") (pinfunction "P$2_B1") (pintype "bidirectional"))
      (node (ref "B03") (pin "B1") (pinfunction "P$2_B1") (pintype "bidirectional"))
      (node (ref "B16") (pin "D2") (pinfunction "OUT_D2") (pintype "output"))
    )
    (net (code "98") (name "P_AC01") (class "Default")
      (node (ref "A03") (pin "D1") (pinfunction "P$2_D1") (pintype "bidirectional"))
      (node (ref "B03") (pin "D1") (pinfunction "P$2_D1") (pintype "bidirectional"))
      (node (ref "B16") (pin "F2") (pinfunction "OUT_F2") (pintype "output"))
    )
    (net (code "99") (name "P_AC02") (class "Default")
      (node (ref "A03") (pin "E1") (pinfunction "P$2_E1") (pintype "bidirectional"))
      (node (ref "B03") (pin "E1") (pinfunction "P$2_E1") (pintype "bidirectional"))
      (node (ref "B16") (pin "J2") (pinfunction "OUT_J2") (pintype "output"))
    )
    (net (code "100") (name "P_AC03") (class "Default")
      (node (ref "A03") (pin "H1") (pinfunction "P$2_H1") (pintype "bidirectional"))
      (node (ref "B03") (pin "H1") (pinfunction "P$2_H1") (pintype "bidirectional"))
      (node (ref "B16") (pin "L2") (pinfunction "OUT_L2") (pintype "output"))
    )
    (net (code "101") (name "P_AC04") (class "Default")
      (node (ref "A03") (pin "J1") (pinfunction "P$2_J1") (pintype "bidirectional"))
      (node (ref "B03") (pin "J1") (pinfunction "P$2_J1") (pintype "bidirectional"))
      (node (ref "B16") (pin "N2") (pinfunction "OUT_N2") (pintype "output"))
    )
    (net (code "102") (name "P_AC05") (class "Default")
      (node (ref "A03") (pin "L1") (pinfunction "P$2_L1") (pintype "bidirectional"))
      (node (ref "B03") (pin "L1") (pinfunction "P$2_L1") (pintype "bidirectional"))
      (node (ref "B16") (pin "R2") (pinfunction "OUT_R2") (pintype "output"))
    )
    (net (code "103") (name "P_AC06") (class "Default")
      (node (ref "A03") (pin "M1") (pinfunction "P$2_M1") (pintype "bidirectional"))
      (node (ref "B03") (pin "M1") (pinfunction "P$2_M1") (pintype "bidirectional"))
      (node (ref "B17") (pin "D2") (pinfunction "OUT_D2") (pintype "output"))
    )
    (net (code "104") (name "P_AC07") (class "Default")
      (node (ref "A03") (pin "P1") (pinfunction "P$2_P1") (pintype "bidirectional"))
      (node (ref "B03") (pin "P1") (pinfunction "P$2_P1") (pintype "bidirectional"))
      (node (ref "B17") (pin "F2") (pinfunction "OUT_F2") (pintype "output"))
    )
    (net (code "105") (name "P_AC08") (class "Default")
      (node (ref "A03") (pin "S1") (pinfunction "P$2_S1") (pintype "bidirectional"))
      (node (ref "B03") (pin "S1") (pinfunction "P$2_S1") (pintype "bidirectional"))
      (node (ref "B17") (pin "J2") (pinfunction "OUT_J2") (pintype "output"))
    )
    (net (code "106") (name "P_AC09") (class "Default")
      (node (ref "A03") (pin "D2") (pinfunction "P$2_D2") (pintype "bidirectional"))
      (node (ref "B03") (pin "D2") (pinfunction "P$2_D2") (pintype "bidirectional"))
      (node (ref "B17") (pin "L2") (pinfunction "OUT_L2") (pintype "output"))
    )
    (net (code "107") (name "P_AC10") (class "Default")
      (node (ref "A03") (pin "E2") (pinfunction "P$2_E2") (pintype "bidirectional"))
      (node (ref "B03") (pin "E2") (pinfunction "P$2_E2") (pintype "bidirectional"))
      (node (ref "B17") (pin "N2") (pinfunction "OUT_N2") (pintype "output"))
    )
    (net (code "108") (name "P_AC11") (class "Default")
      (node (ref "A03") (pin "H2") (pinfunction "P$2_H2") (pintype "bidirectional"))
      (node (ref "B03") (pin "H2") (pinfunction "P$2_H2") (pintype "bidirectional"))
      (node (ref "B17") (pin "R2") (pinfunction "OUT_R2") (pintype "output"))
    )
    (net (code "109") (name "P_ACCEPT") (class "Default")
      (node (ref "A04") (pin "S2") (pinfunction "P$2_S2") (pintype "bidirectional"))
      (node (ref "B04") (pin "S2") (pinfunction "P$2_S2") (pintype "bidirectional"))
      (node (ref "B07") (pin "S2") (pinfunction "CATHODE_S2") (pintype "passive"))
      (node (ref "B15") (pin "H2") (pinfunction "IN2_H2") (pintype "input"))
    )
    (net (code "110") (name "P_ACCLR") (class "Default")
      (node (ref "A03") (pin "P2") (pinfunction "P$2_P2") (pintype "bidirectional"))
      (node (ref "B03") (pin "P2") (pinfunction "P$2_P2") (pintype "bidirectional"))
      (node (ref "B18") (pin "J2") (pinfunction "OUT_J2") (pintype "output"))
    )
    (net (code "111") (name "P_ADD00") (class "Default")
      (node (ref "A04") (pin "B1") (pinfunction "P$2_B1") (pintype "bidirectional"))
      (node (ref "B04") (pin "B1") (pinfunction "P$2_B1") (pintype "bidirectional"))
      (node (ref "B20") (pin "D2") (pinfunction "OUT_D2") (pintype "output"))
    )
    (net (code "112") (name "P_ADD01") (class "Default")
      (node (ref "A04") (pin "D1") (pinfunction "P$2_D1") (pintype "bidirectional"))
      (node (ref "B04") (pin "D1") (pinfunction "P$2_D1") (pintype "bidirectional"))
      (node (ref "B20") (pin "F2") (pinfunction "OUT_F2") (pintype "output"))
    )
    (net (code "113") (name "P_ADD02") (class "Default")
      (node (ref "A04") (pin "E1") (pinfunction "P$2_E1") (pintype "bidirectional"))
      (node (ref "B04") (pin "E1") (pinfunction "P$2_E1") (pintype "bidirectional"))
      (node (ref "B20") (pin "J2") (pinfunction "OUT_J2") (pintype "output"))
    )
    (net (code "114") (name "P_ADD03") (class "Default")
      (node (ref "A04") (pin "H1") (pinfunction "P$2_H1") (pintype "bidirectional"))
      (node (ref "B04") (pin "H1") (pinfunction "P$2_H1") (pintype "bidirectional"))
      (node (ref "B20") (pin "L2") (pinfunction "OUT_L2") (pintype "output"))
    )
    (net (code "115") (name "P_ADD04") (class "Default")
      (node (ref "A04") (pin "J1") (pinfunction "P$2_J1") (pintype "bidirectional"))
      (node (ref "B04") (pin "J1") (pinfunction "P$2_J1") (pintype "bidirectional"))
      (node (ref "B20") (pin "N2") (pinfunction "OUT_N2") (pintype "output"))
    )
    (net (code "116") (name "P_ADD05") (class "Default")
      (node (ref "A04") (pin "L1") (pinfunction "P$2_L1") (pintype "bidirectional"))
      (node (ref "B04") (pin "L1") (pinfunction "P$2_L1") (pintype "bidirectional"))
      (node (ref "B20") (pin "R2") (pinfunction "OUT_R2") (pintype "output"))
    )
    (net (code "117") (name "P_ADD06") (class "Default")
      (node (ref "A04") (pin "M1") (pinfunction "P$2_M1") (pintype "bidirectional"))
      (node (ref "B04") (pin "M1") (pinfunction "P$2_M1") (pintype "bidirectional"))
      (node (ref "B21") (pin "D2") (pinfunction "OUT_D2") (pintype "output"))
    )
    (net (code "118") (name "P_ADD07") (class "Default")
      (node (ref "A04") (pin "P1") (pinfunction "P$2_P1") (pintype "bidirectional"))
      (node (ref "B04") (pin "P1") (pinfunction "P$2_P1") (pintype "bidirectional"))
      (node (ref "B21") (pin "F2") (pinfunction "OUT_F2") (pintype "output"))
    )
    (net (code "119") (name "P_ADD08") (class "Default")
      (node (ref "A04") (pin "S1") (pinfunction "P$2_S1") (pintype "bidirectional"))
      (node (ref "B04") (pin "S1") (pinfunction "P$2_S1") (pintype "bidirectional"))
      (node (ref "B21") (pin "J2") (pinfunction "OUT_J2") (pintype "output"))
    )
    (net (code "120") (name "P_ADD09") (class "Default")
      (node (ref "A04") (pin "D2") (pinfunction "P$2_D2") (pintype "bidirectional"))
      (node (ref "B04") (pin "D2") (pinfunction "P$2_D2") (pintype "bidirectional"))
      (node (ref "B21") (pin "L2") (pinfunction "OUT_L2") (pintype "output"))
    )
    (net (code "121") (name "P_ADD10") (class "Default")
      (node (ref "A04") (pin "E2") (pinfunction "P$2_E2") (pintype "bidirectional"))
      (node (ref "B04") (pin "E2") (pinfunction "P$2_E2") (pintype "bidirectional"))
      (node (ref "B21") (pin "N2") (pinfunction "OUT_N2") (pintype "output"))
    )
    (net (code "122") (name "P_ADD11") (class "Default")
      (node (ref "A04") (pin "H2") (pinfunction "P$2_H2") (pintype "bidirectional"))
      (node (ref "B04") (pin "H2") (pinfunction "P$2_H2") (pintype "bidirectional"))
      (node (ref "B21") (pin "R2") (pinfunction "OUT_R2") (pintype "output"))
    )
    (net (code "123") (name "P_BAC00") (class "Default")
      (node (ref "A01") (pin "B1") (pinfunction "P$2_B1") (pintype "bidirectional"))
      (node (ref "B01") (pin "B1") (pinfunction "P$2_B1") (pintype "bidirectional"))
      (node (ref "B07") (pin "B1") (pinfunction "CATHODE_B1") (pintype "passive"))
      (node (ref "B10") (pin "H2") (pinfunction "IN2_H2") (pintype "input"))
    )
    (net (code "124") (name "P_BAC01") (class "Default")
      (node (ref "A01") (pin "D1") (pinfunction "P$2_D1") (pintype "bidirectional"))
      (node (ref "B01") (pin "D1") (pinfunction "P$2_D1") (pintype "bidirectional"))
      (node (ref "B07") (pin "D1") (pinfunction "CATHODE_D1") (pintype "passive"))
      (node (ref "B10") (pin "N2") (pinfunction "IN2_N2") (pintype "input"))
    )
    (net (code "125") (name "P_BAC02") (class "Default")
      (node (ref "A01") (pin "E1") (pinfunction "P$2_E1") (pintype "bidirectional"))
      (node (ref "B01") (pin "E1") (pinfunction "P$2_E1") (pintype "bidirectional"))
      (node (ref "B07") (pin "E1") (pinfunction "CATHODE_E1") (pintype "passive"))
      (node (ref "B10") (pin "U2") (pinfunction "IN2_U2") (pintype "input"))
    )
    (net (code "126") (name "P_BAC03") (class "Default")
      (node (ref "A01") (pin "H1") (pinfunction "P$2_H1") (pintype "bidirectional"))
      (node (ref "B01") (pin "H1") (pinfunction "P$2_H1") (pintype "bidirectional"))
      (node (ref "B07") (pin "H1") (pinfunction "CATHODE_H1") (pintype "passive"))
      (node (ref "B11") (pin "H2") (pinfunction "IN2_H2") (pintype "input"))
    )
    (net (code "127") (name "P_BAC04") (class "Default")
      (node (ref "A01") (pin "J1") (pinfunction "P$2_J1") (pintype "bidirectional"))
      (node (ref "B01") (pin "J1") (pinfunction "P$2_J1") (pintype "bidirectional"))
      (node (ref "B07") (pin "J1") (pinfunction "CATHODE_J1") (pintype "passive"))
      (node (ref "B11") (pin "N2") (pinfunction "IN2_N2") (pintype "input"))
    )
    (net (code "128") (name "P_BAC05") (class "Default")
      (node (ref "A01") (pin "L1") (pinfunction "P$2_L1") (pintype "bidirectional"))
      (node (ref "B01") (pin "L1") (pinfunction "P$2_L1") (pintype "bidirectional"))
      (node (ref "B07") (pin "L1") (pinfunction "CATHODE_L1") (pintype "passive"))
      (node (ref "B11") (pin "U2") (pinfunction "IN2_U2") (pintype "input"))
    )
    (net (code "129") (name "P_BAC06") (class "Default")
      (node (ref "A01") (pin "M1") (pinfunction "P$2_M1") (pintype "bidirectional"))
      (node (ref "B01") (pin "M1") (pinfunction "P$2_M1") (pintype "bidirectional"))
      (node (ref "B07") (pin "M1") (pinfunction "CATHODE_M1") (pintype "passive"))
      (node (ref "B12") (pin "H2") (pinfunction "IN2_H2") (pintype "input"))
    )
    (net (code "130") (name "P_BAC07") (class "Default")
      (node (ref "A01") (pin "P1") (pinfunction "P$2_P1") (pintype "bidirectional"))
      (node (ref "B01") (pin "P1") (pinfunction "P$2_P1") (pintype "bidirectional"))
      (node (ref "B07") (pin "P1") (pinfunction "CATHODE_P1") (pintype "passive"))
      (node (ref "B12") (pin "N2") (pinfunction "IN2_N2") (pintype "input"))
    )
    (net (code "131") (name "P_BAC08") (class "Default")
      (node (ref "A01") (pin "S1") (pinfunction "P$2_S1") (pintype "bidirectional"))
      (node (ref "B01") (pin "S1") (pinfunction "P$2_S1") (pintype "bidirectional"))
      (node (ref "B07") (pin "S1") (pinfunction "CATHODE_S1") (pintype "passive"))
      (node (ref "B12") (pin "U2") (pinfunction "IN2_U2") (pintype "input"))
    )
    (net (code "132") (name "P_BAC09") (class "Default")
      (node (ref "A01") (pin "D2") (pinfunction "P$2_D2") (pintype "bidirectional"))
      (node (ref "B01") (pin "D2") (pinfunction "P$2_D2") (pintype "bidirectional"))
      (node (ref "B07") (pin "D2") (pinfunction "CATHODE_D2") (pintype "passive"))
      (node (ref "B13") (pin "H2") (pinfunction "IN2_H2") (pintype "input"))
    )
    (net (code "133") (name "P_BAC10") (class "Default")
      (node (ref "A01") (pin "E2") (pinfunction "P$2_E2") (pintype "bidirectional"))
      (node (ref "B01") (pin "E2") (pinfunction "P$2_E2") (pintype "bidirectional"))
      (node (ref "B07") (pin "E2") (pinfunction "CATHODE_E2") (pintype "passive"))
      (node (ref "B13") (pin "N2") (pinfunction "IN2_N2") (pintype "input"))
    )
    (net (code "134") (name "P_BAC11") (class "Default")
      (node (ref "A01") (pin "H2") (pinfunction "P$2_H2") (pintype "bidirectional"))
      (node (ref "B01") (pin "H2") (pinfunction "P$2_H2") (pintype "bidirectional"))
      (node (ref "B07") (pin "H2") (pinfunction "CATHODE_H2") (pintype "passive"))
      (node (ref "B13") (pin "U2") (pinfunction "IN2_U2") (pintype "input"))
    )
    (net (code "135") (name "P_BREAK") (class "Default")
      (node (ref "A04") (pin "P2") (pinfunction "P$2_P2") (pintype "bidirectional"))
      (node (ref "B04") (pin "P2") (pinfunction "P$2_P2") (pintype "bidirectional"))
      (node (ref "B07") (pin "P2") (pinfunction "CATHODE_P2") (pintype "passive"))
      (node (ref "B14") (pin "U2") (pinfunction "IN2_U2") (pintype "input"))
      (node (ref "B22") (pin "V2") (pinfunction "P$1_V2") (pintype "input"))
      (node (ref "B23") (pin "V2") (pinfunction "P$1_V2") (pintype "input"))
    )
    (net (code "136") (name "P_BRKRQ") (class "Default")
      (node (ref "A04") (pin "K2") (pinfunction "P$2_K2") (pintype "bidirectional"))
      (node (ref "B04") (pin "K2") (pinfunction "P$2_K2") (pintype "bidirectional"))
      (node (ref "B18") (pin "N2") (pinfunction "OUT_N2") (pintype "output"))
    )
    (net (code "137") (name "P_CAINCR") (class "Default")
      (node (ref "A05") (pin "M2") (pinfunction "P$2_M2") (pintype "bidirectional"))
      (node (ref "B05") (pin "M2") (pinfunction "P$2_M2") (pintype "bidirectional"))
      (node (ref "B19") (pin "J2") (pinfunction "OUT_J2") (pintype "output"))
    )
    (net (code "138") (name "P_DATA00") (class "Default")
      (node (ref "A05") (pin "B1") (pinfunction "P$2_B1") (pintype "bidirectional"))
      (node (ref "B05") (pin "B1") (pinfunction "P$2_B1") (pintype "bidirectional"))
      (node (ref "B22") (pin "D2") (pinfunction "OUT_D2") (pintype "output"))
    )
    (net (code "139") (name "P_DATA01") (class "Default")
      (node (ref "A05") (pin "D1") (pinfunction "P$2_D1") (pintype "bidirectional"))
      (node (ref "B05") (pin "D1") (pinfunction "P$2_D1") (pintype "bidirectional"))
      (node (ref "B22") (pin "F2") (pinfunction "OUT_F2") (pintype "output"))
    )
    (net (code "140") (name "P_DATA02") (class "Default")
      (node (ref "A05") (pin "E1") (pinfunction "P$2_E1") (pintype "bidirectional"))
      (node (ref "B05") (pin "E1") (pinfunction "P$2_E1") (pintype "bidirectional"))
      (node (ref "B22") (pin "J2") (pinfunction "OUT_J2") (pintype "output"))
    )
    (net (code "141") (name "P_DATA03") (class "Default")
      (node (ref "A05") (pin "H1") (pinfunction "P$2_H1") (pintype "bidirectional"))
      (node (ref "B05") (pin "H1") (pinfunction "P$2_H1") (pintype "bidirectional"))
      (node (ref "B22") (pin "L2") (pinfunction "OUT_L2") (pintype "output"))
    )
    (net (code "142") (name "P_DATA04") (class "Default")
      (node (ref "A05") (pin "J1") (pinfunction "P$2_J1") (pintype "bidirectional"))
      (node (ref "B05") (pin "J1") (pinfunction "P$2_J1") (pintype "bidirectional"))
      (node (ref "B22") (pin "N2") (pinfunction "OUT_N2") (pintype "output"))
    )
    (net (code "143") (name "P_DATA05") (class "Default")
      (node (ref "A05") (pin "L1") (pinfunction "P$2_L1") (pintype "bidirectional"))
      (node (ref "B05") (pin "L1") (pinfunction "P$2_L1") (pintype "bidirectional"))
      (node (ref "B22") (pin "R2") (pinfunction "OUT_R2") (pintype "output"))
    )
    (net (code "144") (name "P_DATA06") (class "Default")
      (node (ref "A05") (pin "M1") (pinfunction "P$2_M1") (pintype "bidirectional"))
      (node (ref "B05") (pin "M1") (pinfunction "P$2_M1") (pintype "bidirectional"))
      (node (ref "B23") (pin "D2") (pinfunction "OUT_D2") (pintype "output"))
    )
    (net (code "145") (name "P_DATA07") (class "Default")
      (node (ref "A05") (pin "P1") (pinfunction "P$2_P1") (pintype "bidirectional"))
      (node (ref "B05") (pin "P1") (pinfunction "P$2_P1") (pintype "bidirectional"))
      (node (ref "B23") (pin "F2") (pinfunction "OUT_F2") (pintype "output"))
    )
    (net (code "146") (name "P_DATA08") (class "Default")
      (node (ref "A05") (pin "S1") (pinfunction "P$2_S1") (pintype "bidirectional"))
      (node (ref "B05") (pin "S1") (pinfunction "P$2_S1") (pintype "bidirectional"))
      (node (ref "B23") (pin "J2") (pinfunction "OUT_J2") (pintype "output"))
    )
    (net (code "147") (name "P_DATA09") (class "Default")
      (node (ref "A05") (pin "D2") (pinfunction "P$2_D2") (pintype "bidirectional"))
      (node (ref "B05") (pin "D2") (pinfunction "P$2_D2") (pintype "bidirectional"))
      (node (ref "B23") (pin "L2") (pinfunction "OUT_L2") (pintype "output"))
    )
    (net (code "148") (name "P_DATA10") (class "Default")
      (node (ref "A05") (pin "E2") (pinfunction "P$2_E2") (pintype "bidirectional"))
      (node (ref "B05") (pin "E2") (pinfunction "P$2_E2") (pintype "bidirectional"))
      (node (ref "B23") (pin "N2") (pinfunction "OUT_N2") (pintype "output"))
    )
    (net (code "149") (name "P_DATA11") (class "Default")
      (node (ref "A05") (pin "H2") (pinfunction "P$2_H2") (pintype "bidirectional"))
      (node (ref "B05") (pin "H2") (pinfunction "P$2_H2") (pintype "bidirectional"))
      (node (ref "B23") (pin "R2") (pinfunction "OUT_R2") (pintype "output"))
    )
    (net (code "150") (name "P_DATAIN") (class "Default")
      (node (ref "A04") (pin "M2") (pinfunction "P$2_M2") (pintype "bidirectional"))
      (node (ref "B04") (pin "M2") (pinfunction "P$2_M2") (pintype "bidirectional"))
      (node (ref "B18") (pin "R2") (pinfunction "OUT_R2") (pintype "output"))
    )
    (net (code "151") (name "P_EXTA0") (class "Default")
      (node (ref "A05") (pin "V2") (pinfunction "P$2_V2") (pintype "bidirectional"))
      (node (ref "B05") (pin "V2") (pinfunction "P$2_V2") (pintype "bidirectional"))
      (node (ref "B19") (pin "R2") (pinfunction "OUT_R2") (pintype "output"))
    )
    (net (code "152") (name "P_EXTA1") (class "Default")
      (node (ref "A05") (pin "T2") (pinfunction "P$2_T2") (pintype "bidirectional"))
      (node (ref "B05") (pin "T2") (pinfunction "P$2_T2") (pintype "bidirectional"))
      (node (ref "B19") (pin "N2") (pinfunction "OUT_N2") (pintype "output"))
    )
    (net (code "153") (name "P_EXTA2") (class "Default")
      (node (ref "A05") (pin "S2") (pinfunction "P$2_S2") (pintype "bidirectional"))
      (node (ref "B05") (pin "S2") (pinfunction "P$2_S2") (pintype "bidirectional"))
      (node (ref "B19") (pin "L2") (pinfunction "OUT_L2") (pintype "output"))
    )
    (net (code "154") (name "P_INIT") (class "Default")
      (node (ref "A01") (pin "V2") (pinfunction "P$2_V2") (pintype "bidirectional"))
      (node (ref "A04") (pin "V2") (pinfunction "P$2_V2") (pintype "bidirectional"))
      (node (ref "B01") (pin "V2") (pinfunction "P$2_V2") (pintype "bidirectional"))
      (node (ref "B04") (pin "V2") (pinfunction "P$2_V2") (pintype "bidirectional"))
      (node (ref "B06") (pin "N1") (pinfunction "IN_N1") (pintype "input"))
    )
    (net (code "155") (name "P_IOP1") (class "Default")
      (node (ref "A01") (pin "K2") (pinfunction "P$2_K2") (pintype "bidirectional"))
      (node (ref "B01") (pin "K2") (pinfunction "P$2_K2") (pintype "bidirectional"))
      (node (ref "B06") (pin "A1") (pinfunction "IN1_A1") (pintype "input"))
    )
    (net (code "156") (name "P_IOP2") (class "Default")
      (node (ref "A01") (pin "M2") (pinfunction "P$2_M2") (pintype "bidirectional"))
      (node (ref "B01") (pin "M2") (pinfunction "P$2_M2") (pintype "bidirectional"))
      (node (ref "B06") (pin "D1") (pinfunction "IN_D1") (pintype "input"))
    )
    (net (code "157") (name "P_IOP4") (class "Default")
      (node (ref "A01") (pin "P2") (pinfunction "P$2_P2") (pintype "bidirectional"))
      (node (ref "B01") (pin "P2") (pinfunction "P$2_P2") (pintype "bidirectional"))
      (node (ref "B06") (pin "F1") (pinfunction "IN_F1") (pintype "input"))
    )
    (net (code "158") (name "P_IRQ") (class "Default")
      (node (ref "A03") (pin "M2") (pinfunction "P$2_M2") (pintype "bidirectional"))
      (node (ref "B03") (pin "M2") (pinfunction "P$2_M2") (pintype "bidirectional"))
      (node (ref "B18") (pin "F2") (pinfunction "OUT_F2") (pintype "output"))
    )
    (net (code "159") (name "P_LINE") (class "Default")
      (node (ref "A03") (pin "V2") (pinfunction "P$2_V2") (pintype "bidirectional"))
      (node (ref "B03") (pin "V2") (pinfunction "P$2_V2") (pintype "bidirectional"))
      (node (ref "B18") (pin "L2") (pinfunction "OUT_L2") (pintype "output"))
    )
    (net (code "160") (name "P_MB00") (class "Default")
      (node (ref "A02") (pin "B1") (pinfunction "P$2_B1") (pintype "bidirectional"))
      (node (ref "A06") (pin "B1") (pinfunction "CATHODE_B1") (pintype "passive"))
      (node (ref "A07") (pin "H2") (pinfunction "IN2_H2") (pintype "input"))
      (node (ref "B02") (pin "B1") (pinfunction "P$2_B1") (pintype "bidirectional"))
    )
    (net (code "161") (name "P_MB01") (class "Default")
      (node (ref "A02") (pin "D1") (pinfunction "P$2_D1") (pintype "bidirectional"))
      (node (ref "A06") (pin "D1") (pinfunction "CATHODE_D1") (pintype "passive"))
      (node (ref "A07") (pin "N2") (pinfunction "IN2_N2") (pintype "input"))
      (node (ref "B02") (pin "D1") (pinfunction "P$2_D1") (pintype "bidirectional"))
    )
    (net (code "162") (name "P_MB02") (class "Default")
      (node (ref "A02") (pin "E1") (pinfunction "P$2_E1") (pintype "bidirectional"))
      (node (ref "A06") (pin "E1") (pinfunction "CATHODE_E1") (pintype "passive"))
      (node (ref "A07") (pin "U2") (pinfunction "IN2_U2") (pintype "input"))
      (node (ref "B02") (pin "E1") (pinfunction "P$2_E1") (pintype "bidirectional"))
    )
    (net (code "163") (name "P_MB03") (class "Default")
      (node (ref "A02") (pin "J1") (pinfunction "P$2_J1") (pintype "bidirectional"))
      (node (ref "A06") (pin "J1") (pinfunction "CATHODE_J1") (pintype "passive"))
      (node (ref "A08") (pin "N2") (pinfunction "IN2_N2") (pintype "input"))
      (node (ref "B02") (pin "J1") (pinfunction "P$2_J1") (pintype "bidirectional"))
    )
    (net (code "164") (name "P_MB04") (class "Default")
      (node (ref "A02") (pin "M1") (pinfunction "P$2_M1") (pintype "bidirectional"))
      (node (ref "A06") (pin "M1") (pinfunction "CATHODE_M1") (pintype "passive"))
      (node (ref "A09") (pin "H2") (pinfunction "IN2_H2") (pintype "input"))
      (node (ref "B02") (pin "M1") (pinfunction "P$2_M1") (pintype "bidirectional"))
    )
    (net (code "165") (name "P_MB05") (class "Default")
      (node (ref "A02") (pin "S1") (pinfunction "P$2_S1") (pintype "bidirectional"))
      (node (ref "A06") (pin "S1") (pinfunction "CATHODE_S1") (pintype "passive"))
      (node (ref "A09") (pin "U2") (pinfunction "IN2_U2") (pintype "input"))
      (node (ref "B02") (pin "S1") (pinfunction "P$2_S1") (pintype "bidirectional"))
    )
    (net (code "166") (name "P_MB06") (class "Default")
      (node (ref "A02") (pin "E2") (pinfunction "P$2_E2") (pintype "bidirectional"))
      (node (ref "A06") (pin "E2") (pinfunction "CATHODE_E2") (pintype "passive"))
      (node (ref "A10") (pin "N2") (pinfunction "IN2_N2") (pintype "input"))
      (node (ref "B02") (pin "E2") (pinfunction "P$2_E2") (pintype "bidirectional"))
    )
    (net (code "167") (name "P_MB07") (class "Default")
      (node (ref "A02") (pin "K2") (pinfunction "P$2_K2") (pintype "bidirectional"))
      (node (ref "A06") (pin "K2") (pinfunction "CATHODE_K2") (pintype "passive"))
      (node (ref "A11") (pin "H2") (pinfunction "IN2_H2") (pintype "input"))
      (node (ref "B02") (pin "K2") (pinfunction "P$2_K2") (pintype "bidirectional"))
    )
    (net (code "168") (name "P_MB08") (class "Default")
      (node (ref "A02") (pin "P2") (pinfunction "P$2_P2") (pintype "bidirectional"))
      (node (ref "A06") (pin "P2") (pinfunction "CATHODE_P2") (pintype "passive"))
      (node (ref "A11") (pin "U2") (pinfunction "IN2_U2") (pintype "input"))
      (node (ref "B02") (pin "P2") (pinfunction "P$2_P2") (pintype "bidirectional"))
    )
    (net (code "169") (name "P_MB09") (class "Default")
      (node (ref "A02") (pin "S2") (pinfunction "P$2_S2") (pintype "bidirectional"))
      (node (ref "A06") (pin "S2") (pinfunction "CATHODE_S2") (pintype "passive"))
      (node (ref "A12") (pin "H2") (pinfunction "IN2_H2") (pintype "input"))
      (node (ref "B02") (pin "S2") (pinfunction "P$2_S2") (pintype "bidirectional"))
    )
    (net (code "170") (name "P_MB10") (class "Default")
      (node (ref "A02") (pin "T2") (pinfunction "P$2_T2") (pintype "bidirectional"))
      (node (ref "A06") (pin "T2") (pinfunction "CATHODE_T2") (pintype "passive"))
      (node (ref "A12") (pin "N2") (pinfunction "IN2_N2") (pintype "input"))
      (node (ref "B02") (pin "T2") (pinfunction "P$2_T2") (pintype "bidirectional"))
    )
    (net (code "171") (name "P_MB11") (class "Default")
      (node (ref "A02") (pin "V2") (pinfunction "P$2_V2") (pintype "bidirectional"))
      (node (ref "A06") (pin "V2") (pinfunction "CATHODE_V2") (pintype "passive"))
      (node (ref "A12") (pin "U2") (pinfunction "IN2_U2") (pintype "input"))
      (node (ref "B02") (pin "V2") (pinfunction "P$2_V2") (pintype "bidirectional"))
    )
    (net (code "172") (name "P_MBINCR") (class "Default")
      (node (ref "A04") (pin "T2") (pinfunction "P$2_T2") (pintype "bidirectional"))
      (node (ref "B04") (pin "T2") (pinfunction "P$2_T2") (pintype "bidirectional"))
      (node (ref "B19") (pin "D2") (pinfunction "OUT_D2") (pintype "output"))
    )
    (net (code "173") (name "P_RUN") (class "Default")
      (node (ref "A03") (pin "S2") (pinfunction "P$2_S2") (pintype "bidirectional"))
      (node (ref "B03") (pin "S2") (pinfunction "P$2_S2") (pintype "bidirectional"))
      (node (ref "B07") (pin "K2") (pinfunction "CATHODE_K2") (pintype "passive"))
      (node (ref "B14") (pin "H2") (pinfunction "IN2_H2") (pintype "input"))
    )
    (net (code "174") (name "P_SKIP") (class "Default")
      (node (ref "A03") (pin "K2") (pinfunction "P$2_K2") (pintype "bidirectional"))
      (node (ref "B03") (pin "K2") (pinfunction "P$2_K2") (pintype "bidirectional"))
      (node (ref "B18") (pin "D2") (pinfunction "OUT_D2") (pintype "output"))
    )
    (net (code "175") (name "P_TS1") (class "Default")
      (node (ref "A01") (pin "T2") (pinfunction "P$2_T2") (pintype "bidirectional"))
      (node (ref "B01") (pin "T2") (pinfunction "P$2_T2") (pintype "bidirectional"))
      (node (ref "B06") (pin "L1") (pinfunction "IN_L1") (pintype "input"))
    )
    (net (code "176") (name "P_TS3") (class "Default")
      (node (ref "A01") (pin "S2") (pinfunction "P$2_S2") (pintype "bidirectional"))
      (node (ref "B01") (pin "S2") (pinfunction "P$2_S2") (pintype "bidirectional"))
      (node (ref "B06") (pin "J1") (pinfunction "IN_J1") (pintype "input"))
    )
    (net (code "177") (name "P_TT_INST") (class "Default")
      (node (ref "A03") (pin "T2") (pinfunction "P$2_T2") (pintype "bidirectional"))
      (node (ref "B03") (pin "T2") (pinfunction "P$2_T2") (pintype "bidirectional"))
      (node (ref "B07") (pin "M2") (pinfunction "CATHODE_M2") (pintype "passive"))
      (node (ref "B14") (pin "N2") (pinfunction "IN2_N2") (pintype "input"))
    )
    (net (code "178") (name "P_WCOV") (class "Default")
      (node (ref "A05") (pin "P2") (pinfunction "P$2_P2") (pintype "bidirectional"))
      (node (ref "B05") (pin "P2") (pinfunction "P$2_P2") (pintype "bidirectional"))
      (node (ref "B07") (pin "T2") (pinfunction "CATHODE_T2") (pintype "passive"))
      (node (ref "B15") (pin "N2") (pinfunction "IN2_N2") (pintype "input"))
    )
    (net (code "180") (name "unconnected-(A07A-SLOW-PadE2)") (class "Default")
      (node (ref "A07") (pin "E2") (pinfunction "SLOW_E2") (pintype "passive"))
    )
    (net (code "181") (name "unconnected-(A07D-SLOW-PadL2)") (class "Default")
      (node (ref "A07") (pin "L2") (pinfunction "SLOW_L2") (pintype "passive"))
    )
    (net (code "182") (name "unconnected-(A07E-SLOW-PadR2)") (class "Default")
      (node (ref "A07") (pin "R2") (pinfunction "SLOW_R2") (pintype "passive"))
    )
    (net (code "183") (name "unconnected-(A08A-SLOW-PadE2)") (class "Default")
      (node (ref "A08") (pin "E2") (pinfunction "SLOW_E2") (pintype "passive"))
    )
    (net (code "184") (name "unconnected-(A08D-SLOW-PadL2)") (class "Default")
      (node (ref "A08") (pin "L2") (pinfunction "SLOW_L2") (pintype "passive"))
    )
    (net (code "185") (name "unconnected-(A08E-SLOW-PadR2)") (class "Default")
      (node (ref "A08") (pin "R2") (pinfunction "SLOW_R2") (pintype "passive"))
    )
    (net (code "186") (name "unconnected-(A09A-SLOW-PadE2)") (class "Default")
      (node (ref "A09") (pin "E2") (pinfunction "SLOW_E2") (pintype "passive"))
    )
    (net (code "187") (name "unconnected-(A09D-SLOW-PadL2)") (class "Default")
      (node (ref "A09") (pin "L2") (pinfunction "SLOW_L2") (pintype "passive"))
    )
    (net (code "188") (name "unconnected-(A09E-SLOW-PadR2)") (class "Default")
      (node (ref "A09") (pin "R2") (pinfunction "SLOW_R2") (pintype "passive"))
    )
    (net (code "189") (name "unconnected-(A10A-SLOW-PadE2)") (class "Default")
      (node (ref "A10") (pin "E2") (pinfunction "SLOW_E2") (pintype "passive"))
    )
    (net (code "190") (name "unconnected-(A10D-SLOW-PadL2)") (class "Default")
      (node (ref "A10") (pin "L2") (pinfunction "SLOW_L2") (pintype "passive"))
    )
    (net (code "191") (name "unconnected-(A10E-SLOW-PadR2)") (class "Default")
      (node (ref "A10") (pin "R2") (pinfunction "SLOW_R2") (pintype "passive"))
    )
    (net (code "192") (name "unconnected-(A11A-SLOW-PadE2)") (class "Default")
      (node (ref "A11") (pin "E2") (pinfunction "SLOW_E2") (pintype "passive"))
    )
    (net (code "193") (name "unconnected-(A11D-SLOW-PadL2)") (class "Default")
      (node (ref "A11") (pin "L2") (pinfunction "SLOW_L2") (pintype "passive"))
    )
    (net (code "194") (name "unconnected-(A11E-SLOW-PadR2)") (class "Default")
      (node (ref "A11") (pin "R2") (pinfunction "SLOW_R2") (pintype "passive"))
    )
    (net (code "195") (name "unconnected-(A12A-SLOW-PadE2)") (class "Default")
      (node (ref "A12") (pin "E2") (pinfunction "SLOW_E2") (pintype "passive"))
    )
    (net (code "196") (name "unconnected-(A12D-SLOW-PadL2)") (class "Default")
      (node (ref "A12") (pin "L2") (pinfunction "SLOW_L2") (pintype "passive"))
    )
    (net (code "197") (name "unconnected-(A12E-SLOW-PadR2)") (class "Default")
      (node (ref "A12") (pin "R2") (pinfunction "SLOW_R2") (pintype "passive"))
    )
    (net (code "198") (name "unconnected-(B08A-SLOW-PadE2)") (class "Default")
      (node (ref "B08") (pin "E2") (pinfunction "SLOW_E2") (pintype "passive"))
    )
    (net (code "199") (name "unconnected-(B08D-SLOW-PadL2)") (class "Default")
      (node (ref "B08") (pin "L2") (pinfunction "SLOW_L2") (pintype "passive"))
    )
    (net (code "200") (name "unconnected-(B08E-SLOW-PadR2)") (class "Default")
      (node (ref "B08") (pin "R2") (pinfunction "SLOW_R2") (pintype "passive"))
    )
    (net (code "201") (name "unconnected-(B09A-SLOW-PadE2)") (class "Default")
      (node (ref "B09") (pin "E2") (pinfunction "SLOW_E2") (pintype "passive"))
    )
    (net (code "202") (name "unconnected-(B09D-SLOW-PadL2)") (class "Default")
      (node (ref "B09") (pin "L2") (pinfunction "SLOW_L2") (pintype "passive"))
    )
    (net (code "203") (name "unconnected-(B09E-SLOW-PadR2)") (class "Default")
      (node (ref "B09") (pin "R2") (pinfunction "SLOW_R2") (pintype "passive"))
    )
    (net (code "204") (name "unconnected-(B10A-SLOW-PadE2)") (class "Default")
      (node (ref "B10") (pin "E2") (pinfunction "SLOW_E2") (pintype "passive"))
    )
    (net (code "205") (name "unconnected-(B10D-SLOW-PadL2)") (class "Default")
      (node (ref "B10") (pin "L2") (pinfunction "SLOW_L2") (pintype "passive"))
    )
    (net (code "206") (name "unconnected-(B10E-SLOW-PadR2)") (class "Default")
      (node (ref "B10") (pin "R2") (pinfunction "SLOW_R2") (pintype "passive"))
    )
    (net (code "207") (name "unconnected-(B11A-SLOW-PadE2)") (class "Default")
      (node (ref "B11") (pin "E2") (pinfunction "SLOW_E2") (pintype "passive"))
    )
    (net (code "208") (name "unconnected-(B11D-SLOW-PadL2)") (class "Default")
      (node (ref "B11") (pin "L2") (pinfunction "SLOW_L2") (pintype "passive"))
    )
    (net (code "209") (name "unconnected-(B11E-SLOW-PadR2)") (class "Default")
      (node (ref "B11") (pin "R2") (pinfunction "SLOW_R2") (pintype "passive"))
    )
    (net (code "210") (name "unconnected-(B12A-SLOW-PadE2)") (class "Default")
      (node (ref "B12") (pin "E2") (pinfunction "SLOW_E2") (pintype "passive"))
    )
    (net (code "211") (name "unconnected-(B12D-SLOW-PadL2)") (class "Default")
      (node (ref "B12") (pin "L2") (pinfunction "SLOW_L2") (pintype "passive"))
    )
    (net (code "212") (name "unconnected-(B12E-SLOW-PadR2)") (class "Default")
      (node (ref "B12") (pin "R2") (pinfunction "SLOW_R2") (pintype "passive"))
    )
    (net (code "213") (name "unconnected-(B13A-SLOW-PadE2)") (class "Default")
      (node (ref "B13") (pin "E2") (pinfunction "SLOW_E2") (pintype "passive"))
    )
    (net (code "214") (name "unconnected-(B13D-SLOW-PadL2)") (class "Default")
      (node (ref "B13") (pin "L2") (pinfunction "SLOW_L2") (pintype "passive"))
    )
    (net (code "215") (name "unconnected-(B13E-SLOW-PadR2)") (class "Default")
      (node (ref "B13") (pin "R2") (pinfunction "SLOW_R2") (pintype "passive"))
    )
    (net (code "216") (name "unconnected-(B14A-SLOW-PadE2)") (class "Default")
      (node (ref "B14") (pin "E2") (pinfunction "SLOW_E2") (pintype "passive"))
    )
    (net (code "217") (name "unconnected-(B14D-SLOW-PadL2)") (class "Default")
      (node (ref "B14") (pin "L2") (pinfunction "SLOW_L2") (pintype "passive"))
    )
    (net (code "218") (name "unconnected-(B14E-SLOW-PadR2)") (class "Default")
      (node (ref "B14") (pin "R2") (pinfunction "SLOW_R2") (pintype "passive"))
    )
    (net (code "219") (name "unconnected-(B15A-SLOW-PadE2)") (class "Default")
      (node (ref "B15") (pin "E2") (pinfunction "SLOW_E2") (pintype "passive"))
    )
    (net (code "220") (name "unconnected-(B15D-SLOW-PadL2)") (class "Default")
      (node (ref "B15") (pin "L2") (pinfunction "SLOW_L2") (pintype "passive"))
    )
    (net (code "221") (name "~{N_MB03}") (class "Default")
      (node (ref "A08") (pin "D2") (pinfunction "OUT_D2") (pintype "output"))
      (node (ref "A15") (pin "K2") (pinfunction "P$2_K2") (pintype "bidirectional"))
    )
    (net (code "222") (name "~{N_MB04}") (class "Default")
      (node (ref "A08") (pin "S2") (pinfunction "OUT_S2") (pintype "output"))
      (node (ref "A15") (pin "P2") (pinfunction "P$2_P2") (pintype "bidirectional"))
    )
    (net (code "223") (name "~{N_MB05}") (class "Default")
      (node (ref "A09") (pin "K2") (pinfunction "OUT_K2") (pintype "output"))
      (node (ref "A15") (pin "T2") (pinfunction "P$2_T2") (pintype "bidirectional"))
    )
    (net (code "224") (name "~{N_MB06}") (class "Default")
      (node (ref "A10") (pin "D2") (pinfunction "OUT_D2") (pintype "output"))
      (node (ref "A16") (pin "D2") (pinfunction "P$2_D2") (pintype "bidirectional"))
    )
    (net (code "225") (name "~{N_MB07}") (class "Default")
      (node (ref "A10") (pin "S2") (pinfunction "OUT_S2") (pintype "output"))
      (node (ref "A16") (pin "H2") (pinfunction "P$2_H2") (pintype "bidirectional"))
    )
    (net (code "226") (name "~{N_MB08}") (class "Default")
      (node (ref "A11") (pin "K2") (pinfunction "OUT_K2") (pintype "output"))
      (node (ref "A16") (pin "M2") (pinfunction "P$2_M2") (pintype "bidirectional"))
    )
    (net (code "227") (name "~{P_MB03}") (class "Default")
      (node (ref "A02") (pin "H1") (pinfunction "P$2_H1") (pintype "bidirectional"))
      (node (ref "A06") (pin "H1") (pinfunction "CATHODE_H1") (pintype "passive"))
      (node (ref "A08") (pin "H2") (pinfunction "IN2_H2") (pintype "input"))
      (node (ref "B02") (pin "H1") (pinfunction "P$2_H1") (pintype "bidirectional"))
    )
    (net (code "228") (name "~{P_MB04}") (class "Default")
      (node (ref "A02") (pin "L1") (pinfunction "P$2_L1") (pintype "bidirectional"))
      (node (ref "A06") (pin "L1") (pinfunction "CATHODE_L1") (pintype "passive"))
      (node (ref "A08") (pin "U2") (pinfunction "IN2_U2") (pintype "input"))
      (node (ref "B02") (pin "L1") (pinfunction "P$2_L1") (pintype "bidirectional"))
    )
    (net (code "229") (name "~{P_MB05}") (class "Default")
      (node (ref "A02") (pin "P1") (pinfunction "P$2_P1") (pintype "bidirectional"))
      (node (ref "A06") (pin "P1") (pinfunction "CATHODE_P1") (pintype "passive"))
      (node (ref "A09") (pin "N2") (pinfunction "IN2_N2") (pintype "input"))
      (node (ref "B02") (pin "P1") (pinfunction "P$2_P1") (pintype "bidirectional"))
    )
    (net (code "230") (name "~{P_MB06}") (class "Default")
      (node (ref "A02") (pin "D2") (pinfunction "P$2_D2") (pintype "bidirectional"))
      (node (ref "A06") (pin "D2") (pinfunction "CATHODE_D2") (pintype "passive"))
      (node (ref "A10") (pin "H2") (pinfunction "IN2_H2") (pintype "input"))
      (node (ref "B02") (pin "D2") (pinfunction "P$2_D2") (pintype "bidirectional"))
    )
    (net (code "231") (name "~{P_MB07}") (class "Default")
      (node (ref "A02") (pin "H2") (pinfunction "P$2_H2") (pintype "bidirectional"))
      (node (ref "A06") (pin "H2") (pinfunction "CATHODE_H2") (pintype "passive"))
      (node (ref "A10") (pin "U2") (pinfunction "IN2_U2") (pintype "input"))
      (node (ref "B02") (pin "H2") (pinfunction "P$2_H2") (pintype "bidirectional"))
    )
    (net (code "232") (name "~{P_MB08}") (class "Default")
      (node (ref "A02") (pin "M2") (pinfunction "P$2_M2") (pintype "bidirectional"))
      (node (ref "A06") (pin "M2") (pinfunction "CATHODE_M2") (pintype "passive"))
      (node (ref "A11") (pin "N2") (pinfunction "IN2_N2") (pintype "input"))
      (node (ref "B02") (pin "M2") (pinfunction "P$2_M2") (pintype "bidirectional"))
    )
  )
)
